# Index_Registers_-_1_1.net
KiCad netlist of a schematic drawn in EAGLE
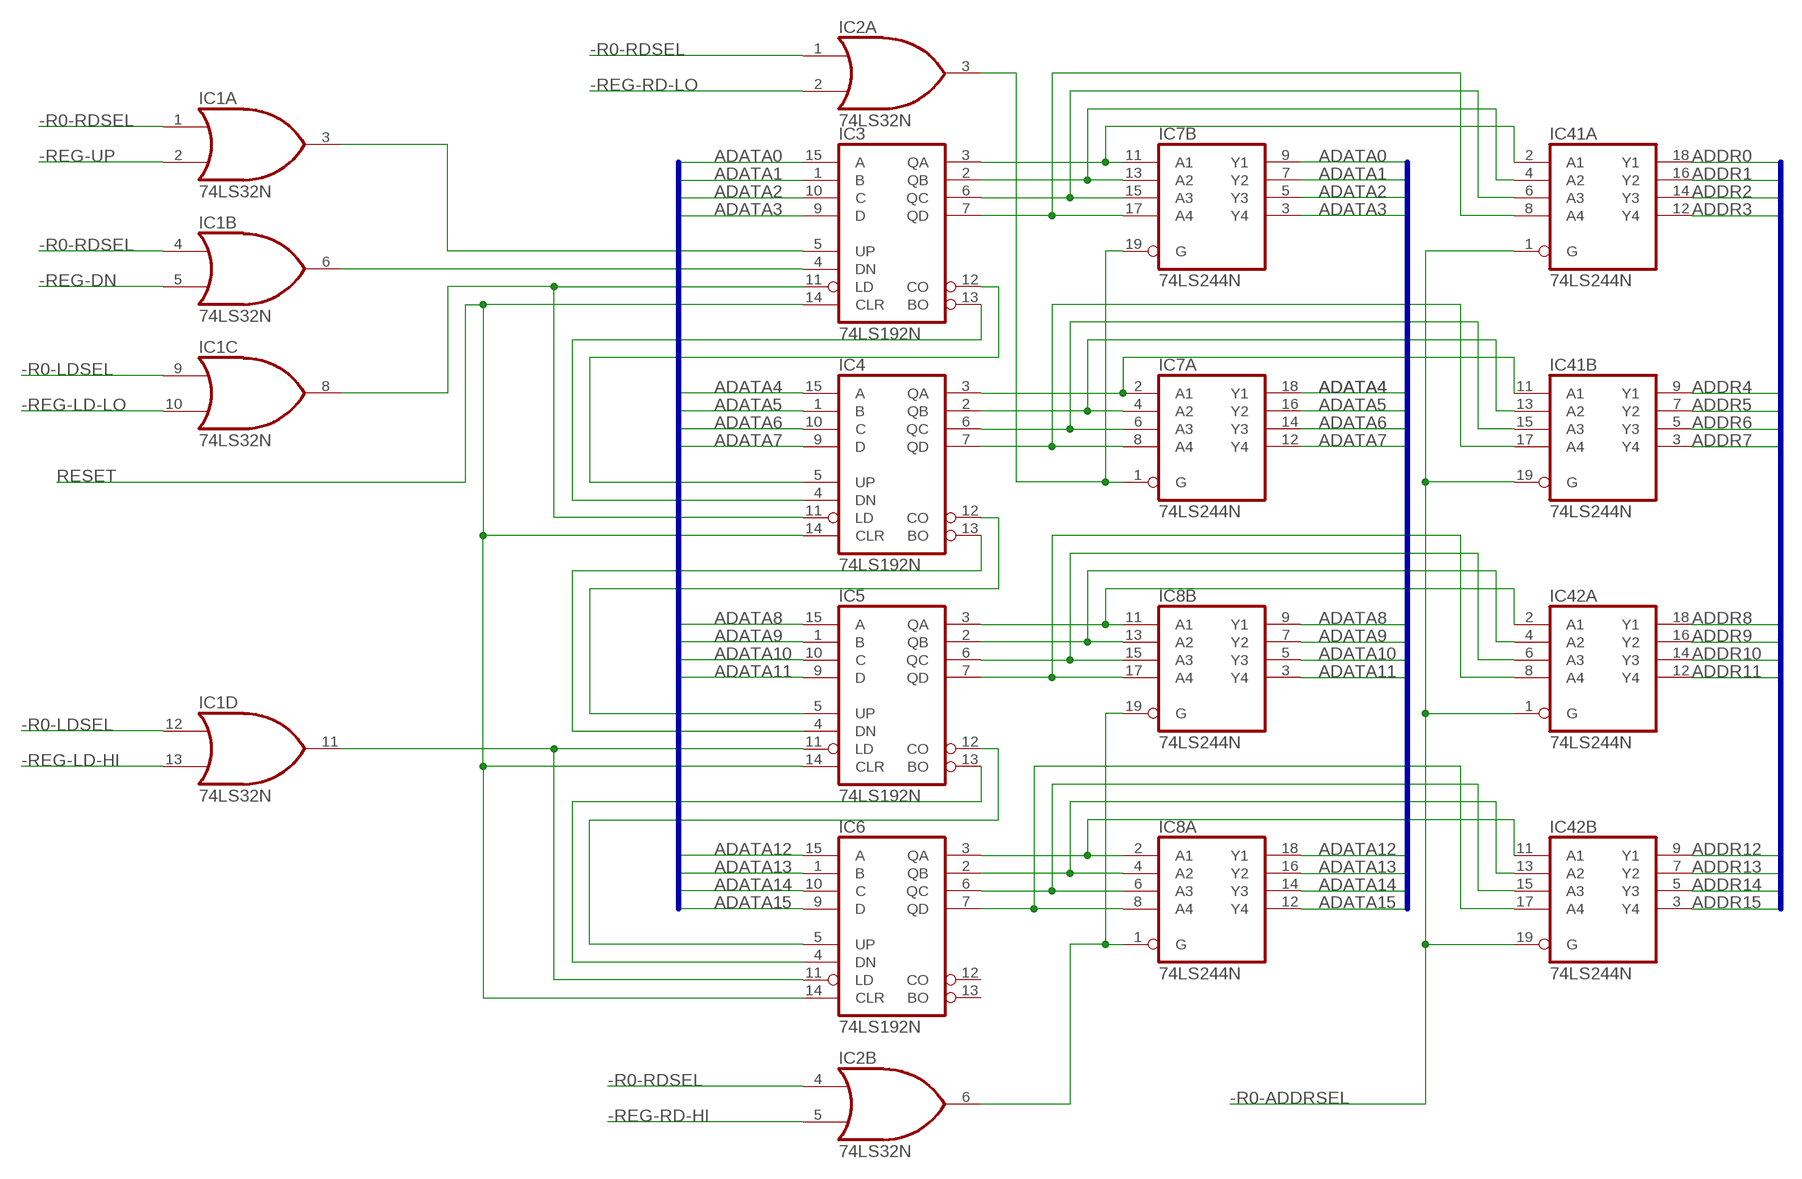
[diagram p0: schematic, sheet 1]
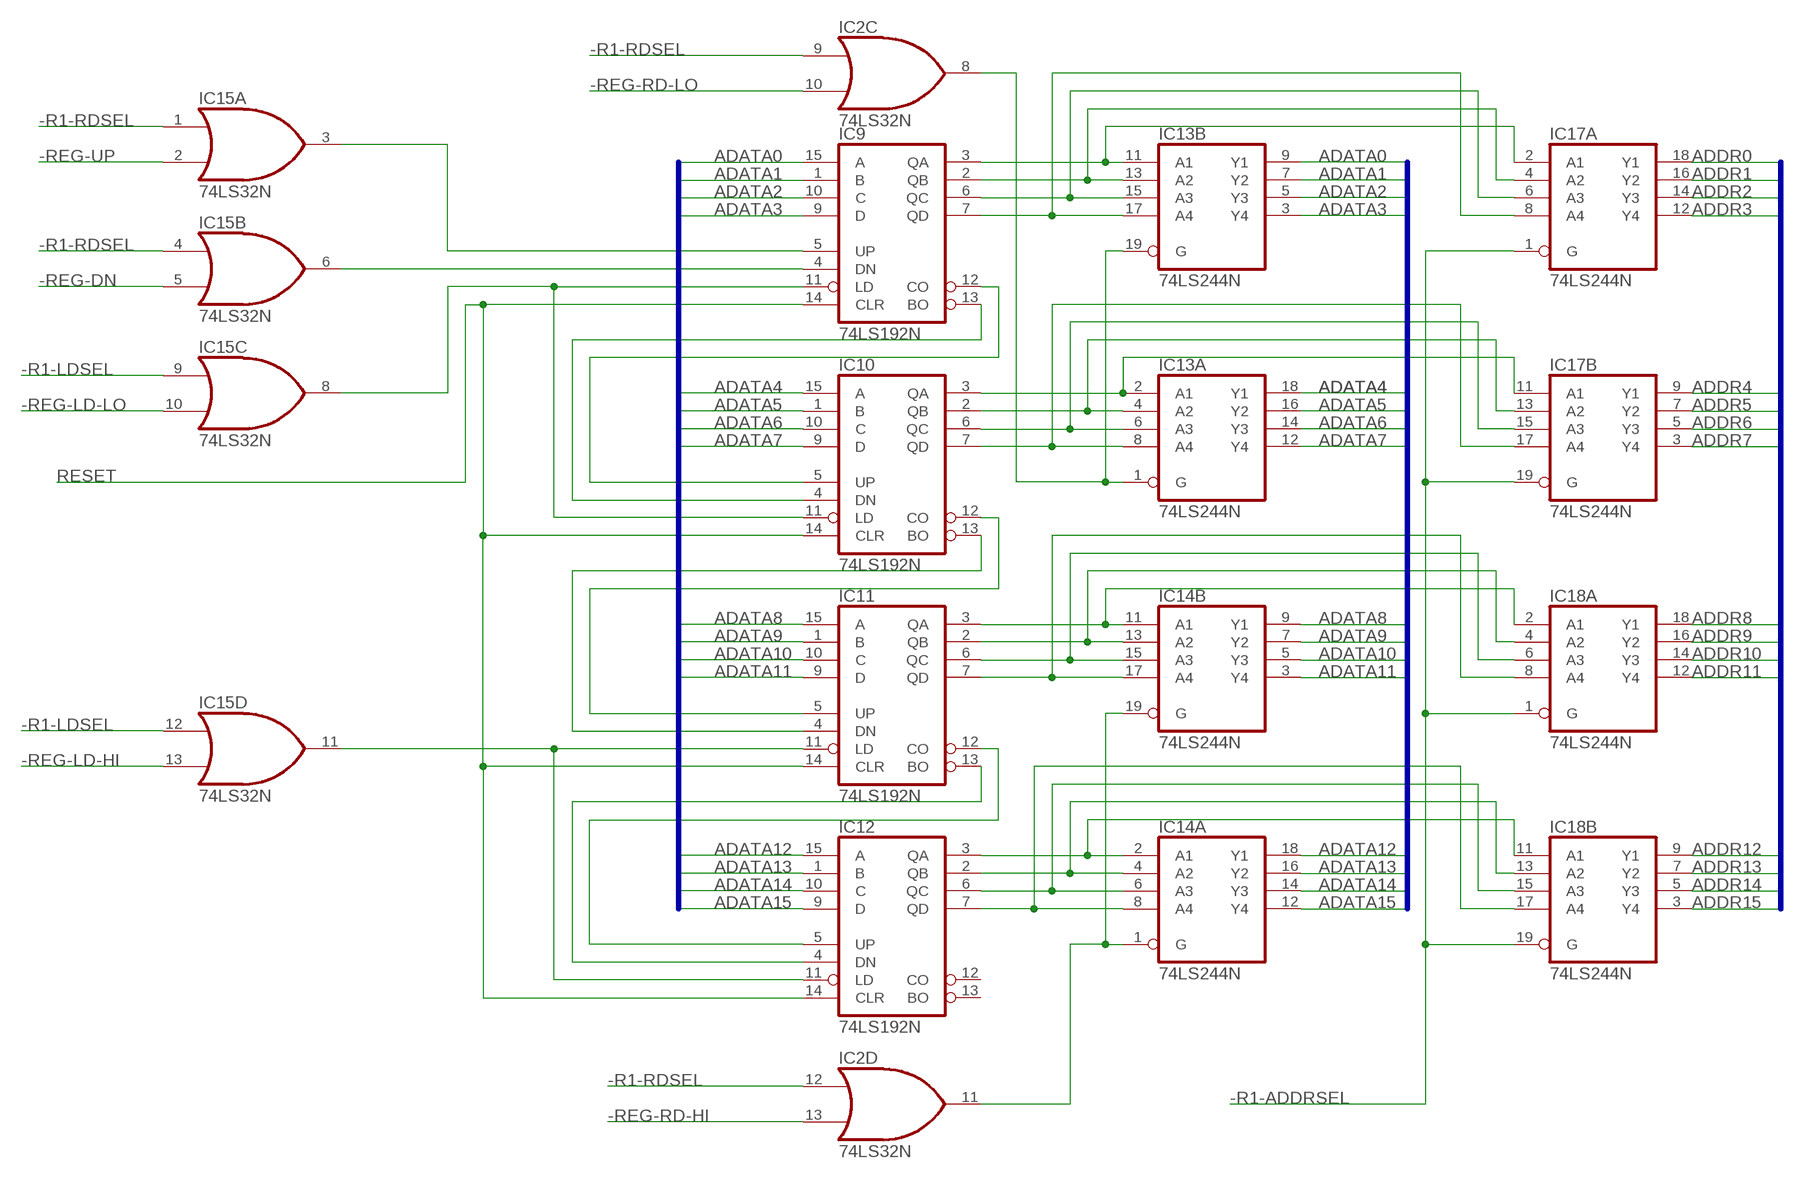
[diagram p1: schematic, sheet 2]
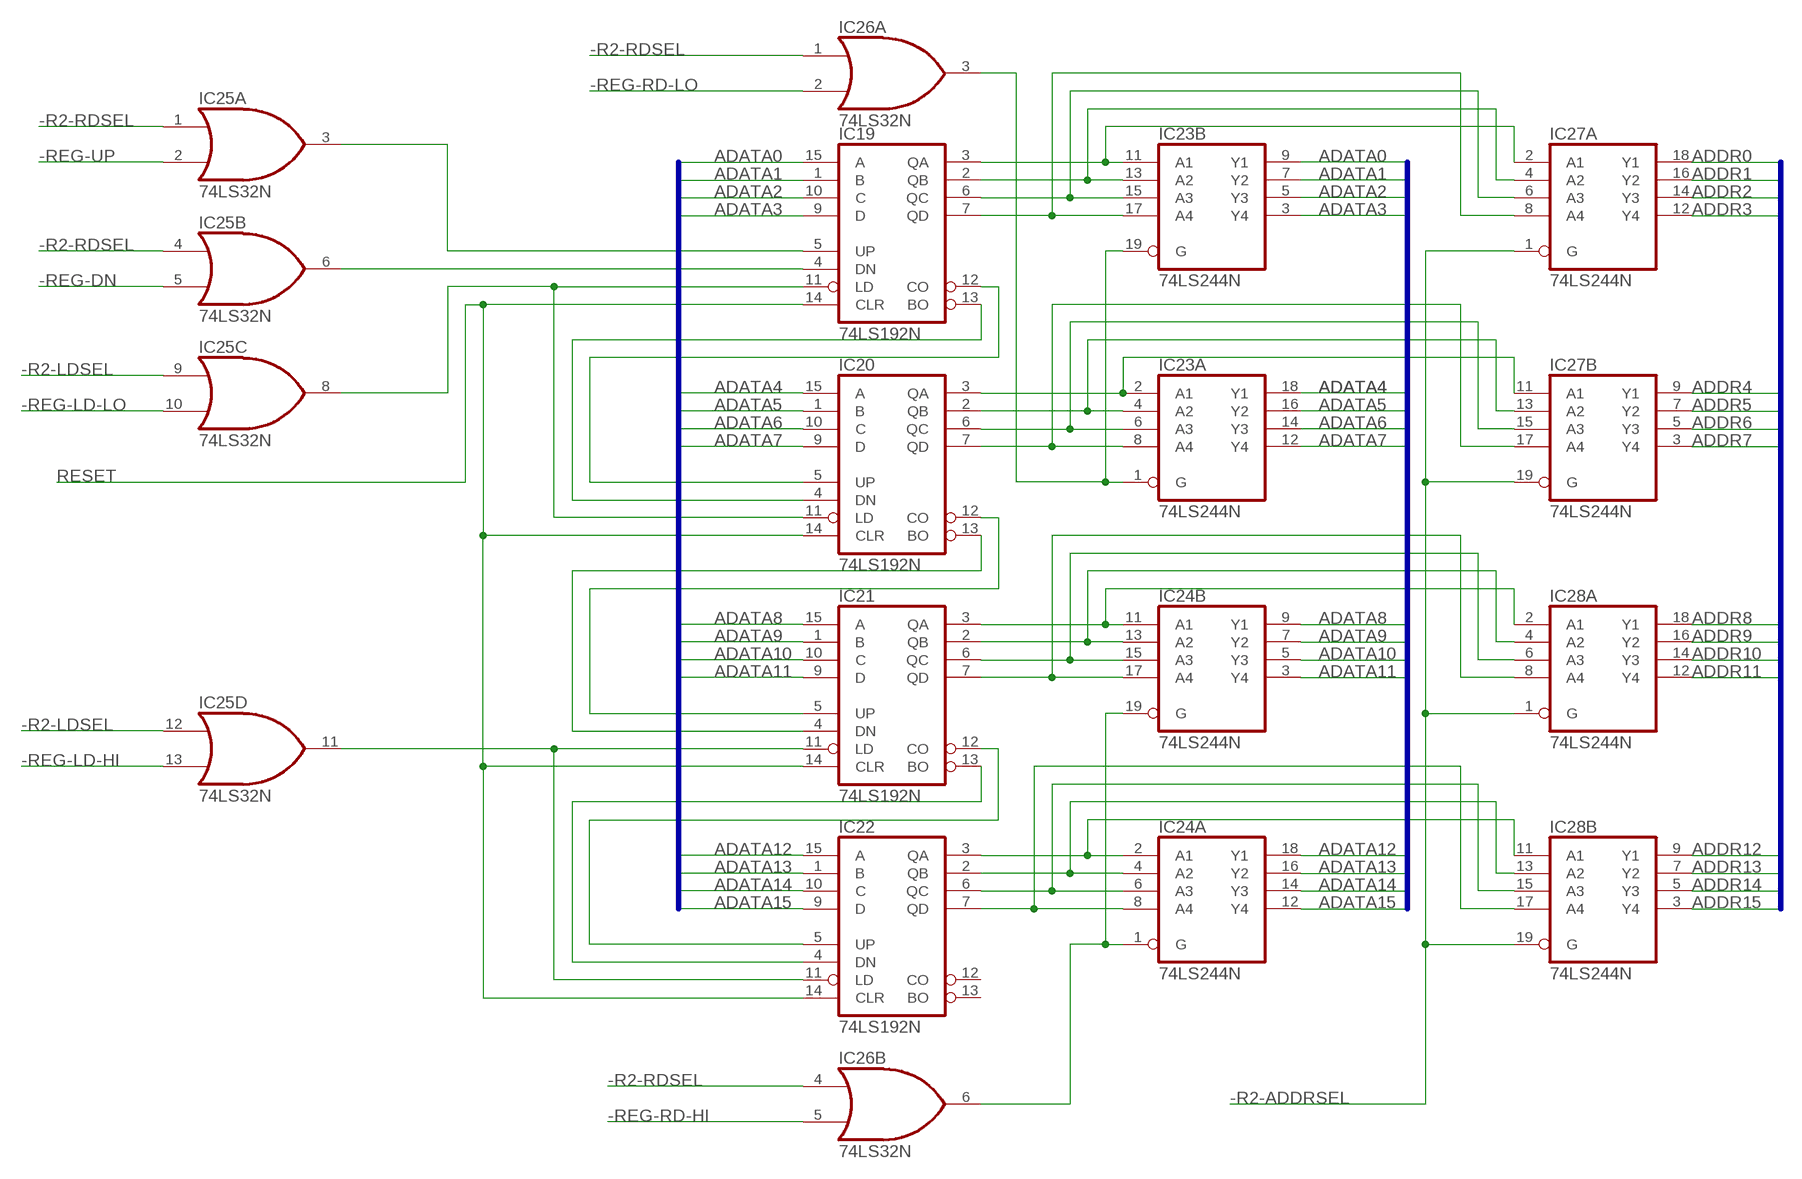
[diagram p2: schematic, sheet 3]
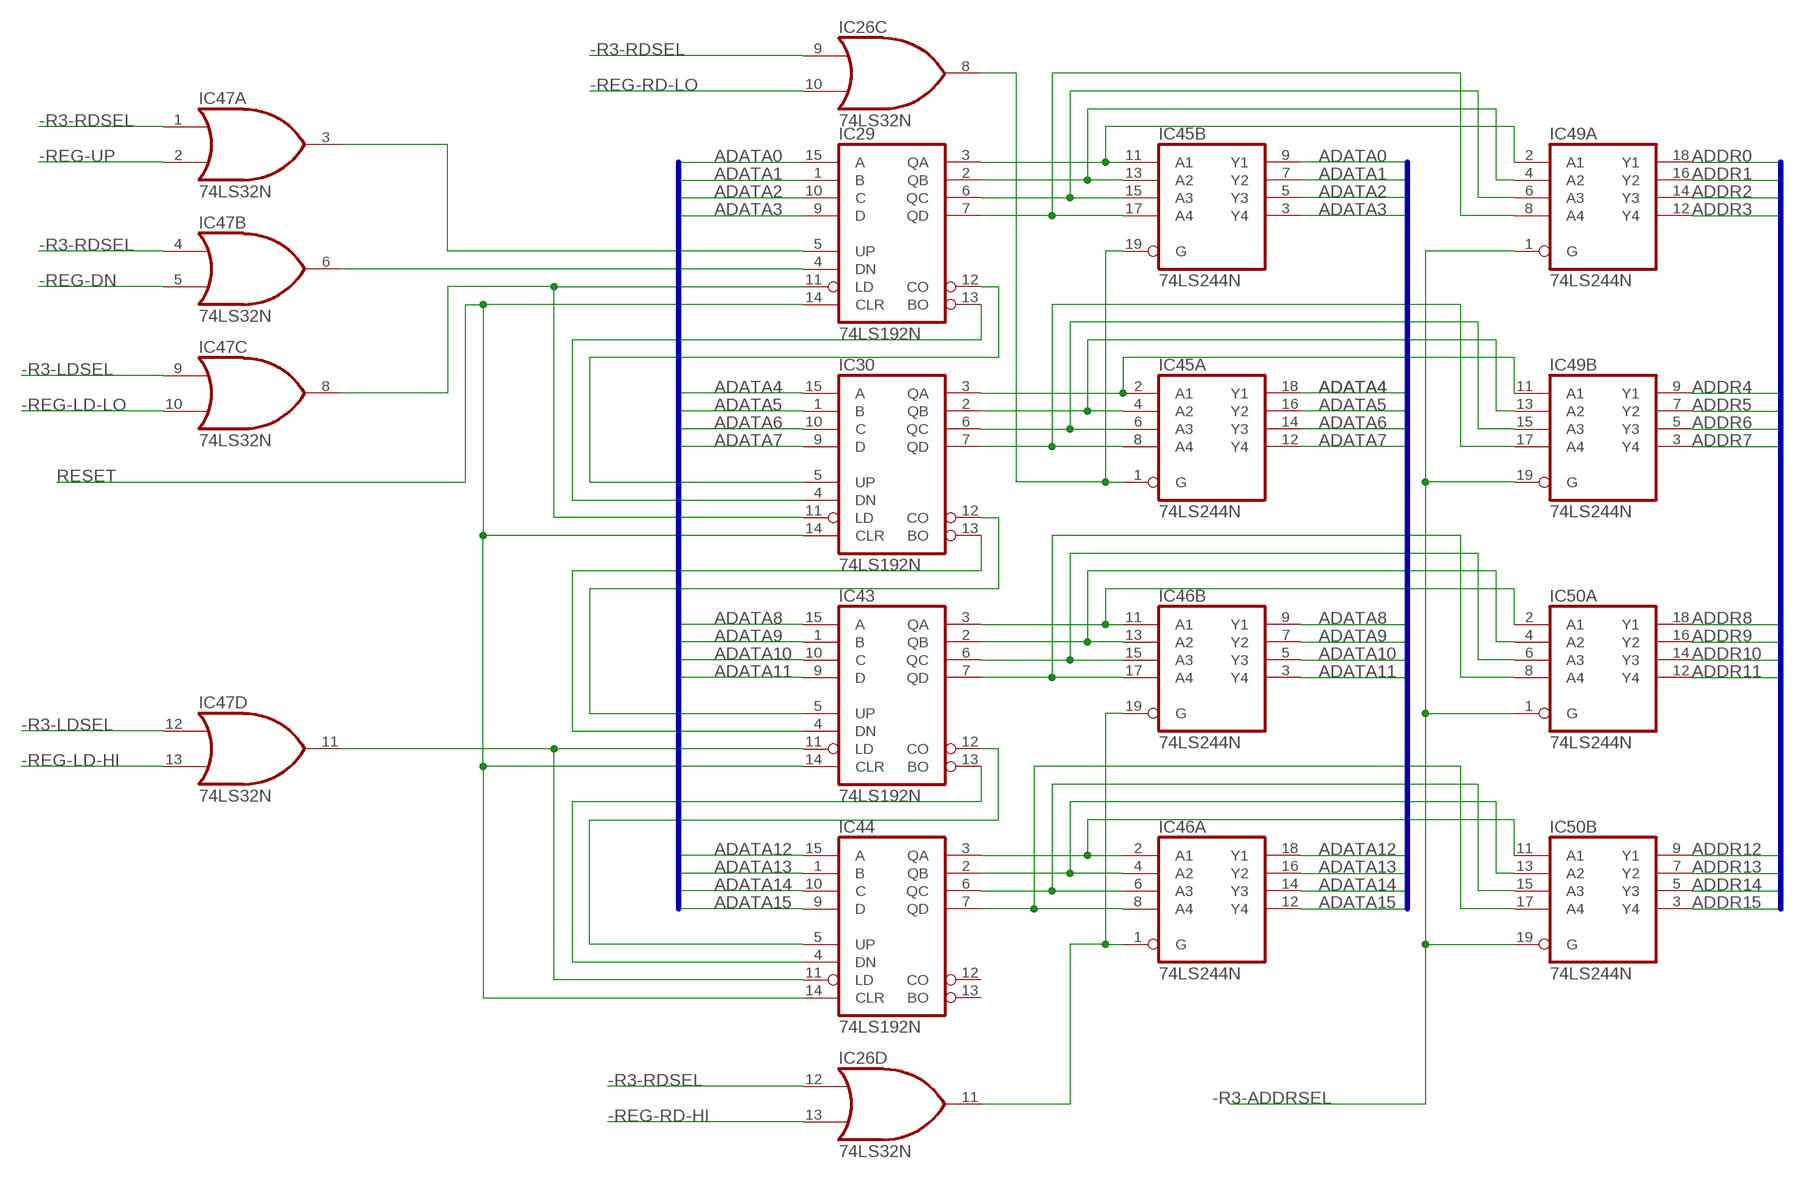
[diagram p3: schematic, sheet 4]
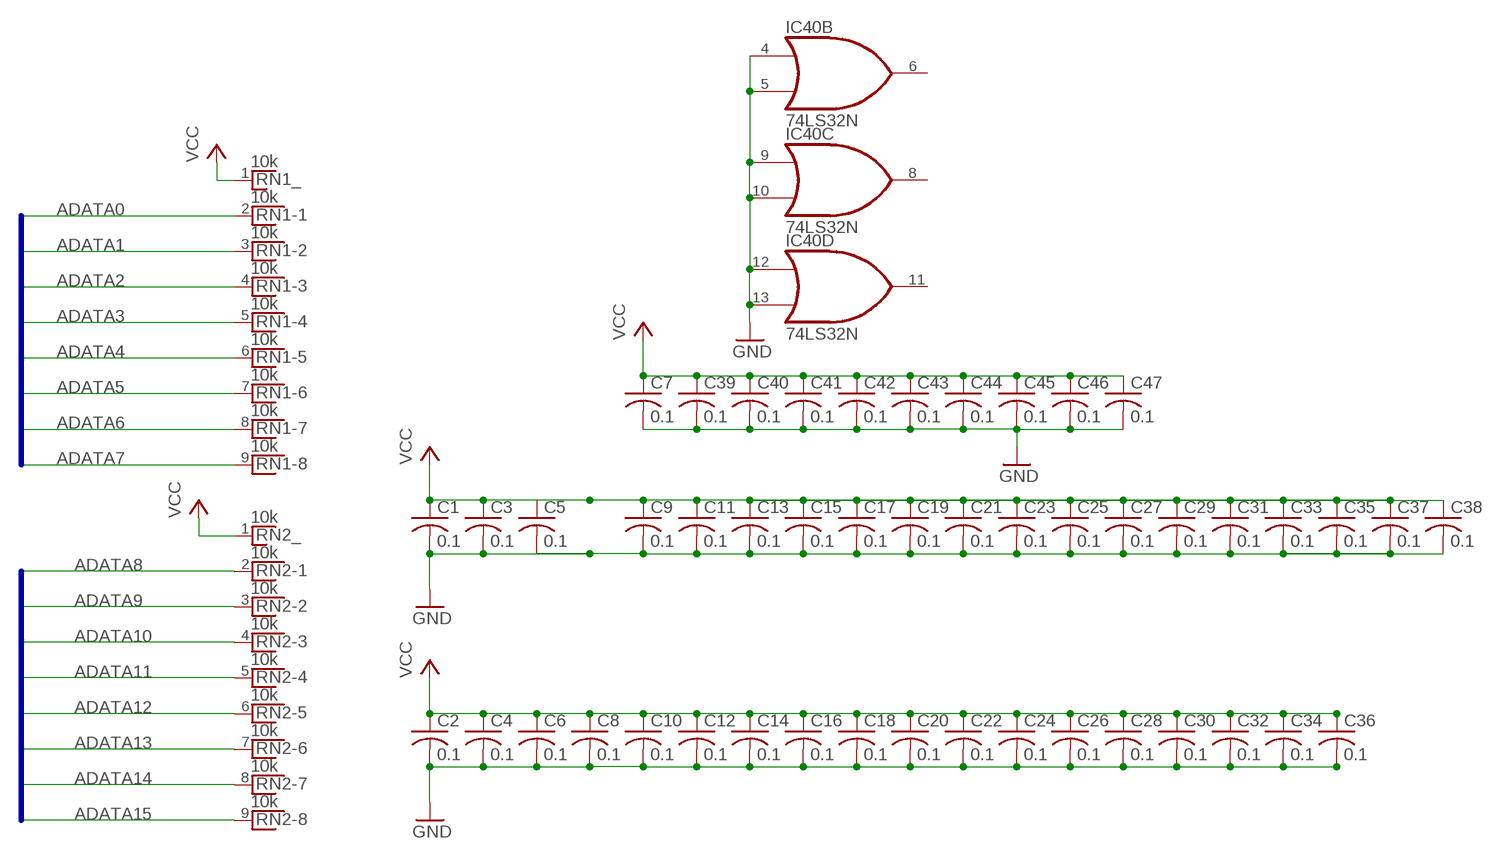
[diagram p4: schematic, sheet 5]
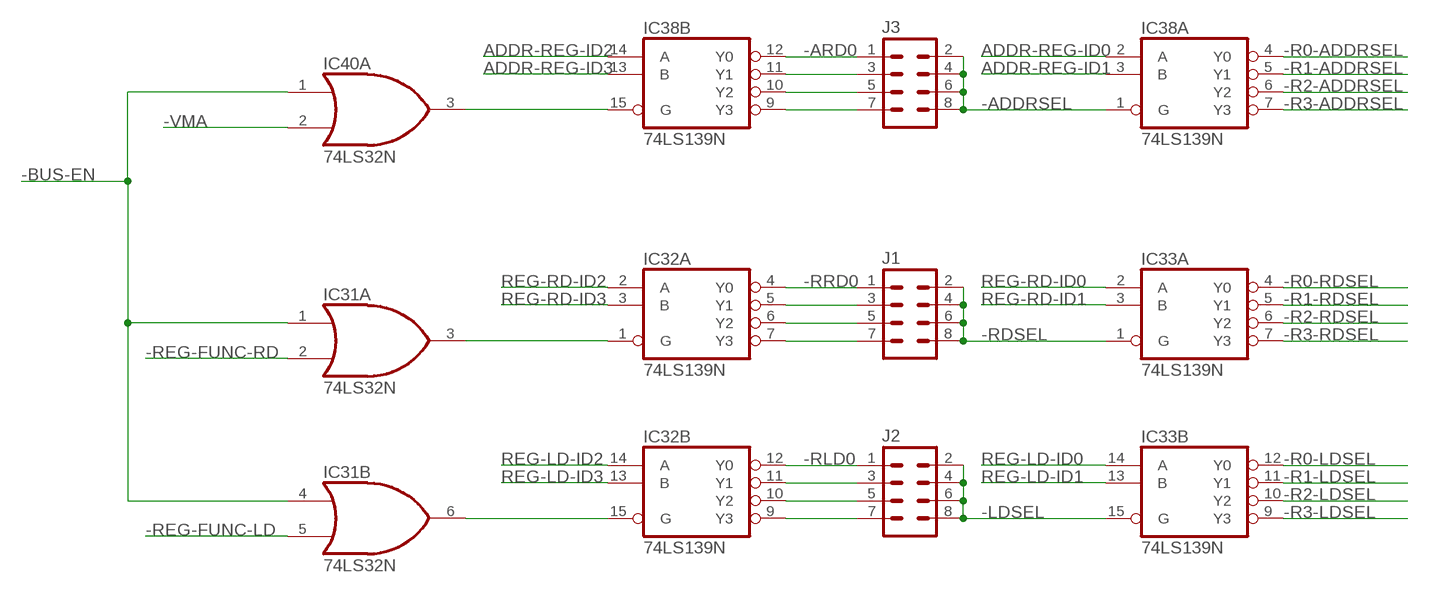
[diagram p5: schematic, sheet 6]
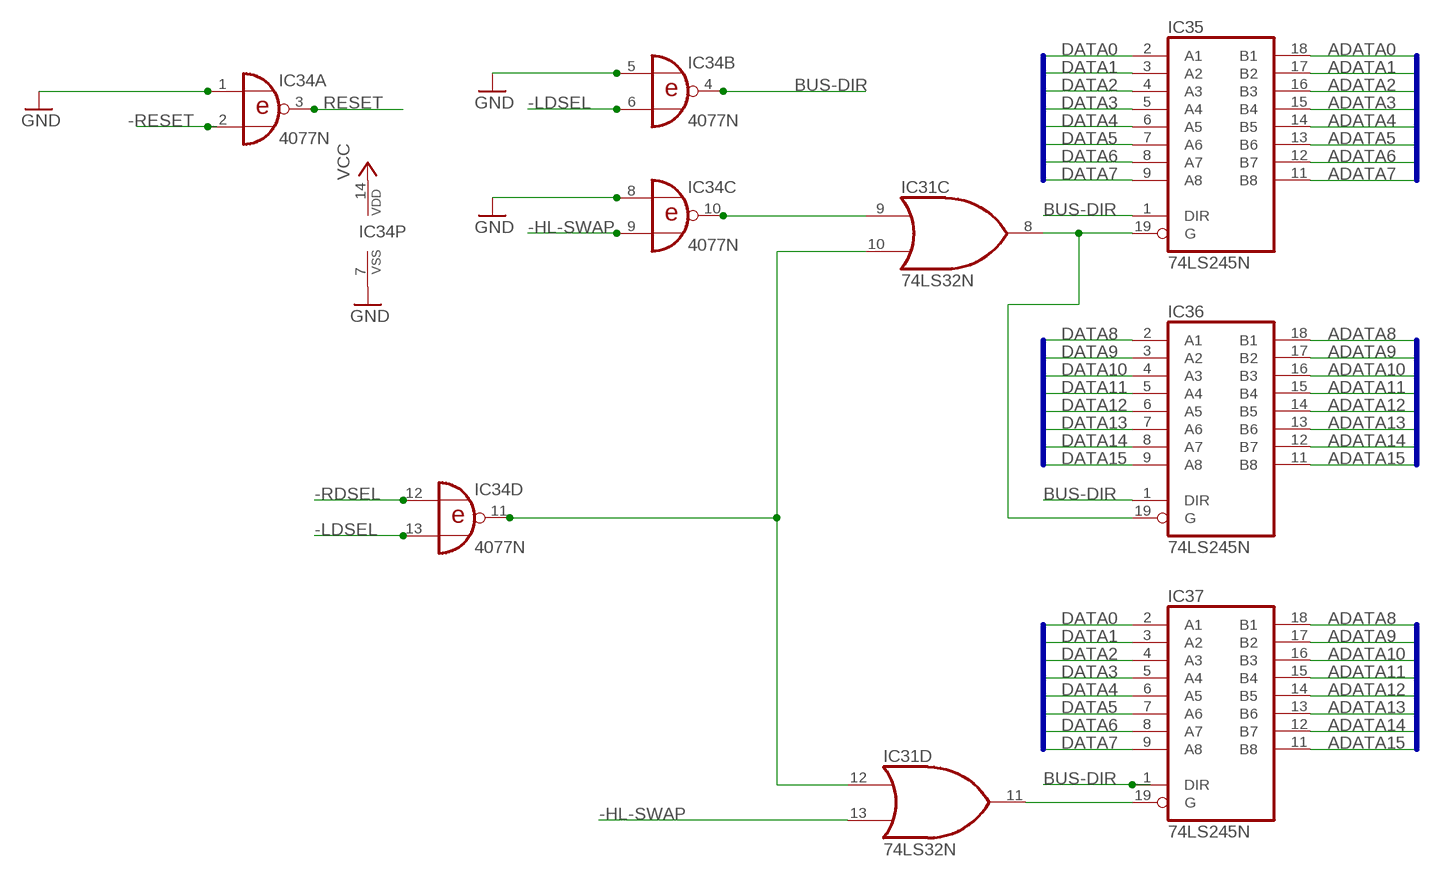
[diagram p6: schematic, sheet 7]
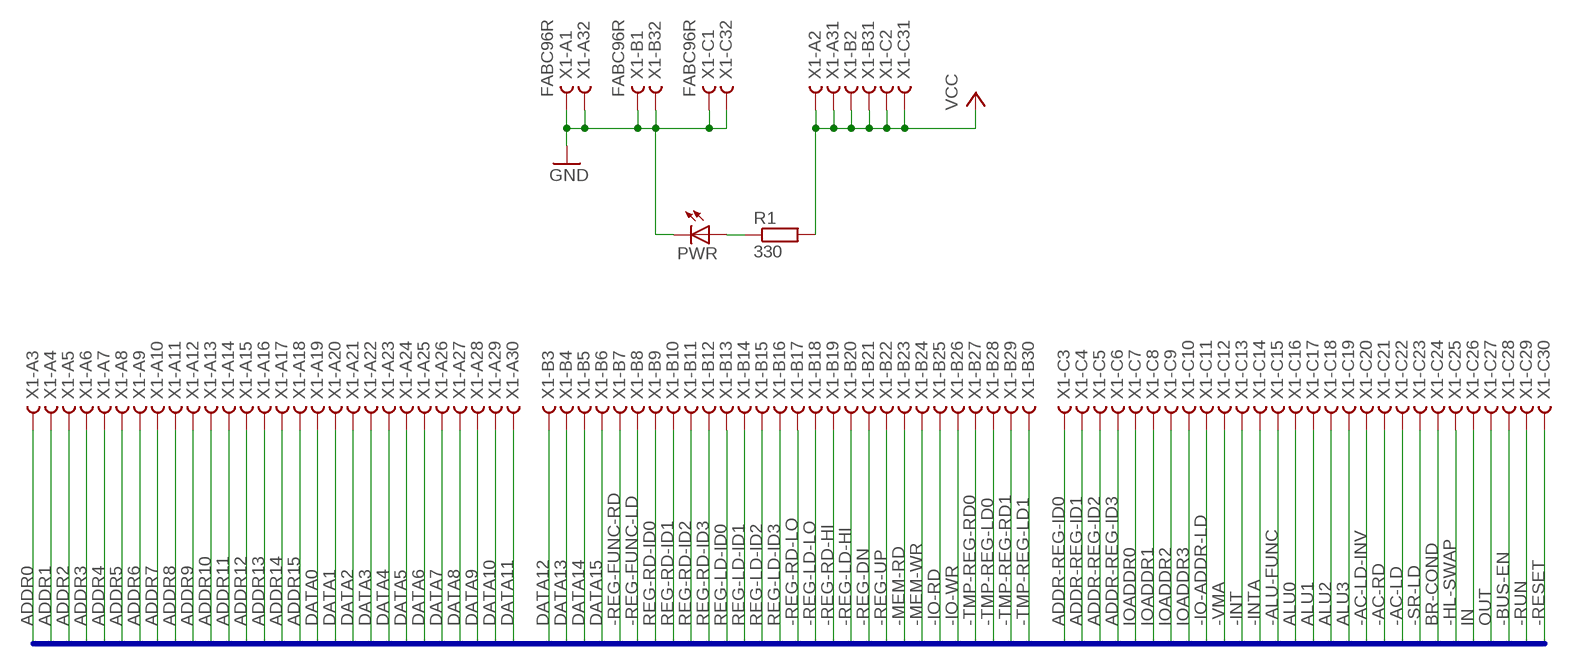
[diagram p7: schematic, sheet 8]

(export (version "E")
  (design (tool "Eeschema 10.0.6"))
  (components
    (comp (ref "PWR")
      (value "LED5MM")
      (footprint "eagle-import:LED5MM")
      (libsource (lib "eagle-import") (part "LED5MM"))
    )
    (comp (ref "R1")
      (value "330")
      (footprint "eagle-import:0207_10")
      (libsource (lib "eagle-import") (part "R0207/10"))
    )
    (comp (ref "X1")
      (value "FABC96R")
      (footprint "eagle-import:FABC96R")
      (libsource (lib "eagle-import") (part "FABC96R"))
    )
    (comp (ref "C1")
      (value "0.1")
      (footprint "eagle-import:C025-040X050")
      (libsource (lib "eagle-import") (part "C-US025-040X050"))
    )
    (comp (ref "C2")
      (value "0.1")
      (footprint "eagle-import:C025-040X050")
      (libsource (lib "eagle-import") (part "C-US025-040X050"))
    )
    (comp (ref "C3")
      (value "0.1")
      (footprint "eagle-import:C025-040X050")
      (libsource (lib "eagle-import") (part "C-US025-040X050"))
    )
    (comp (ref "C4")
      (value "0.1")
      (footprint "eagle-import:C025-040X050")
      (libsource (lib "eagle-import") (part "C-US025-040X050"))
    )
    (comp (ref "C5")
      (value "0.1")
      (footprint "eagle-import:C025-040X050")
      (libsource (lib "eagle-import") (part "C-US025-040X050"))
    )
    (comp (ref "C6")
      (value "0.1")
      (footprint "eagle-import:C025-040X050")
      (libsource (lib "eagle-import") (part "C-US025-040X050"))
    )
    (comp (ref "C7")
      (value "0.1")
      (footprint "eagle-import:C025-040X050")
      (libsource (lib "eagle-import") (part "C-US025-040X050"))
    )
    (comp (ref "C8")
      (value "0.1")
      (footprint "eagle-import:C025-040X050")
      (libsource (lib "eagle-import") (part "C-US025-040X050"))
    )
    (comp (ref "C9")
      (value "0.1")
      (footprint "eagle-import:C025-040X050")
      (libsource (lib "eagle-import") (part "C-US025-040X050"))
    )
    (comp (ref "C10")
      (value "0.1")
      (footprint "eagle-import:C025-040X050")
      (libsource (lib "eagle-import") (part "C-US025-040X050"))
    )
    (comp (ref "C11")
      (value "0.1")
      (footprint "eagle-import:C025-040X050")
      (libsource (lib "eagle-import") (part "C-US025-040X050"))
    )
    (comp (ref "C12")
      (value "0.1")
      (footprint "eagle-import:C025-040X050")
      (libsource (lib "eagle-import") (part "C-US025-040X050"))
    )
    (comp (ref "C13")
      (value "0.1")
      (footprint "eagle-import:C025-040X050")
      (libsource (lib "eagle-import") (part "C-US025-040X050"))
    )
    (comp (ref "C14")
      (value "0.1")
      (footprint "eagle-import:C025-040X050")
      (libsource (lib "eagle-import") (part "C-US025-040X050"))
    )
    (comp (ref "C15")
      (value "0.1")
      (footprint "eagle-import:C025-040X050")
      (libsource (lib "eagle-import") (part "C-US025-040X050"))
    )
    (comp (ref "C16")
      (value "0.1")
      (footprint "eagle-import:C025-040X050")
      (libsource (lib "eagle-import") (part "C-US025-040X050"))
    )
    (comp (ref "C17")
      (value "0.1")
      (footprint "eagle-import:C025-040X050")
      (libsource (lib "eagle-import") (part "C-US025-040X050"))
    )
    (comp (ref "C18")
      (value "0.1")
      (footprint "eagle-import:C025-040X050")
      (libsource (lib "eagle-import") (part "C-US025-040X050"))
    )
    (comp (ref "C19")
      (value "0.1")
      (footprint "eagle-import:C025-040X050")
      (libsource (lib "eagle-import") (part "C-US025-040X050"))
    )
    (comp (ref "C20")
      (value "0.1")
      (footprint "eagle-import:C025-040X050")
      (libsource (lib "eagle-import") (part "C-US025-040X050"))
    )
    (comp (ref "C21")
      (value "0.1")
      (footprint "eagle-import:C025-040X050")
      (libsource (lib "eagle-import") (part "C-US025-040X050"))
    )
    (comp (ref "C22")
      (value "0.1")
      (footprint "eagle-import:C025-040X050")
      (libsource (lib "eagle-import") (part "C-US025-040X050"))
    )
    (comp (ref "C23")
      (value "0.1")
      (footprint "eagle-import:C025-040X050")
      (libsource (lib "eagle-import") (part "C-US025-040X050"))
    )
    (comp (ref "C24")
      (value "0.1")
      (footprint "eagle-import:C025-040X050")
      (libsource (lib "eagle-import") (part "C-US025-040X050"))
    )
    (comp (ref "C25")
      (value "0.1")
      (footprint "eagle-import:C025-040X050")
      (libsource (lib "eagle-import") (part "C-US025-040X050"))
    )
    (comp (ref "C26")
      (value "0.1")
      (footprint "eagle-import:C025-040X050")
      (libsource (lib "eagle-import") (part "C-US025-040X050"))
    )
    (comp (ref "C27")
      (value "0.1")
      (footprint "eagle-import:C025-040X050")
      (libsource (lib "eagle-import") (part "C-US025-040X050"))
    )
    (comp (ref "C28")
      (value "0.1")
      (footprint "eagle-import:C025-040X050")
      (libsource (lib "eagle-import") (part "C-US025-040X050"))
    )
    (comp (ref "C29")
      (value "0.1")
      (footprint "eagle-import:C025-040X050")
      (libsource (lib "eagle-import") (part "C-US025-040X050"))
    )
    (comp (ref "C30")
      (value "0.1")
      (footprint "eagle-import:C025-040X050")
      (libsource (lib "eagle-import") (part "C-US025-040X050"))
    )
    (comp (ref "C31")
      (value "0.1")
      (footprint "eagle-import:C025-040X050")
      (libsource (lib "eagle-import") (part "C-US025-040X050"))
    )
    (comp (ref "C32")
      (value "0.1")
      (footprint "eagle-import:C025-040X050")
      (libsource (lib "eagle-import") (part "C-US025-040X050"))
    )
    (comp (ref "C33")
      (value "0.1")
      (footprint "eagle-import:C025-040X050")
      (libsource (lib "eagle-import") (part "C-US025-040X050"))
    )
    (comp (ref "C34")
      (value "0.1")
      (footprint "eagle-import:C025-040X050")
      (libsource (lib "eagle-import") (part "C-US025-040X050"))
    )
    (comp (ref "C35")
      (value "0.1")
      (footprint "eagle-import:C025-040X050")
      (libsource (lib "eagle-import") (part "C-US025-040X050"))
    )
    (comp (ref "C36")
      (value "0.1")
      (footprint "eagle-import:C025-040X050")
      (libsource (lib "eagle-import") (part "C-US025-040X050"))
    )
    (comp (ref "C37")
      (value "0.1")
      (footprint "eagle-import:C025-040X050")
      (libsource (lib "eagle-import") (part "C-US025-040X050"))
    )
    (comp (ref "C38")
      (value "0.1")
      (footprint "eagle-import:C025-040X050")
      (libsource (lib "eagle-import") (part "C-US025-040X050"))
    )
    (comp (ref "C39")
      (value "0.1")
      (footprint "eagle-import:C025-040X050")
      (libsource (lib "eagle-import") (part "C-US025-040X050"))
    )
    (comp (ref "C40")
      (value "0.1")
      (footprint "eagle-import:C025-040X050")
      (libsource (lib "eagle-import") (part "C-US025-040X050"))
    )
    (comp (ref "C41")
      (value "0.1")
      (footprint "eagle-import:C025-040X050")
      (libsource (lib "eagle-import") (part "C-US025-040X050"))
    )
    (comp (ref "C42")
      (value "0.1")
      (footprint "eagle-import:C025-040X050")
      (libsource (lib "eagle-import") (part "C-US025-040X050"))
    )
    (comp (ref "C43")
      (value "0.1")
      (footprint "eagle-import:C025-040X050")
      (libsource (lib "eagle-import") (part "C-US025-040X050"))
    )
    (comp (ref "C44")
      (value "0.1")
      (footprint "eagle-import:C025-040X050")
      (libsource (lib "eagle-import") (part "C-US025-040X050"))
    )
    (comp (ref "C45")
      (value "0.1")
      (footprint "eagle-import:C025-040X050")
      (libsource (lib "eagle-import") (part "C-US025-040X050"))
    )
    (comp (ref "C46")
      (value "0.1")
      (footprint "eagle-import:C025-040X050")
      (libsource (lib "eagle-import") (part "C-US025-040X050"))
    )
    (comp (ref "C47")
      (value "0.1")
      (footprint "eagle-import:C025-040X050")
      (libsource (lib "eagle-import") (part "C-US025-040X050"))
    )
    (comp (ref "IC40")
      (value "74LS32N")
      (footprint "eagle-import:DIL14")
      (libsource (lib "eagle-import") (part "7432NLS"))
    )
    (comp (ref "RN1")
      (value "10k")
      (footprint "eagle-import:RN-9")
      (libsource (lib "eagle-import") (part "RNX8"))
    )
    (comp (ref "RN2")
      (value "10k")
      (footprint "eagle-import:RN-9")
      (libsource (lib "eagle-import") (part "RNX8"))
    )
    (comp (ref "IC31")
      (value "74LS32N")
      (footprint "eagle-import:DIL14")
      (libsource (lib "eagle-import") (part "7432NLS"))
    )
    (comp (ref "IC34")
      (value "4077N")
      (footprint "eagle-import:DIL14")
      (libsource (lib "eagle-import") (part "4077N"))
    )
    (comp (ref "IC35")
      (value "74LS245N")
      (footprint "eagle-import:DIL20")
      (libsource (lib "eagle-import") (part "74245NLS"))
    )
    (comp (ref "IC36")
      (value "74LS245N")
      (footprint "eagle-import:DIL20")
      (libsource (lib "eagle-import") (part "74245NLS"))
    )
    (comp (ref "IC37")
      (value "74LS245N")
      (footprint "eagle-import:DIL20")
      (libsource (lib "eagle-import") (part "74245NLS"))
    )
    (comp (ref "IC19")
      (value "74LS192N")
      (footprint "eagle-import:DIL16")
      (libsource (lib "eagle-import") (part "74192NLS"))
    )
    (comp (ref "IC20")
      (value "74LS192N")
      (footprint "eagle-import:DIL16")
      (libsource (lib "eagle-import") (part "74192NLS"))
    )
    (comp (ref "IC21")
      (value "74LS192N")
      (footprint "eagle-import:DIL16")
      (libsource (lib "eagle-import") (part "74192NLS"))
    )
    (comp (ref "IC22")
      (value "74LS192N")
      (footprint "eagle-import:DIL16")
      (libsource (lib "eagle-import") (part "74192NLS"))
    )
    (comp (ref "IC23")
      (value "74LS244N")
      (footprint "eagle-import:DIL20")
      (libsource (lib "eagle-import") (part "74xx-us_74244NLS"))
    )
    (comp (ref "IC24")
      (value "74LS244N")
      (footprint "eagle-import:DIL20")
      (libsource (lib "eagle-import") (part "74xx-us_74244NLS"))
    )
    (comp (ref "IC25")
      (value "74LS32N")
      (footprint "eagle-import:DIL14")
      (libsource (lib "eagle-import") (part "7432NLS"))
    )
    (comp (ref "IC26")
      (value "74LS32N")
      (footprint "eagle-import:DIL14")
      (libsource (lib "eagle-import") (part "7432NLS"))
    )
    (comp (ref "IC27")
      (value "74LS244N")
      (footprint "eagle-import:DIL20")
      (libsource (lib "eagle-import") (part "74xx-us_88_74244NLS"))
    )
    (comp (ref "IC28")
      (value "74LS244N")
      (footprint "eagle-import:DIL20")
      (libsource (lib "eagle-import") (part "74xx-us_88_74244NLS"))
    )
    (comp (ref "IC1")
      (value "74LS32N")
      (footprint "eagle-import:DIL14")
      (libsource (lib "eagle-import") (part "7432NLS"))
    )
    (comp (ref "IC2")
      (value "74LS32N")
      (footprint "eagle-import:DIL14")
      (libsource (lib "eagle-import") (part "7432NLS"))
    )
    (comp (ref "IC3")
      (value "74LS192N")
      (footprint "eagle-import:DIL16")
      (libsource (lib "eagle-import") (part "74192NLS"))
    )
    (comp (ref "IC4")
      (value "74LS192N")
      (footprint "eagle-import:DIL16")
      (libsource (lib "eagle-import") (part "74192NLS"))
    )
    (comp (ref "IC5")
      (value "74LS192N")
      (footprint "eagle-import:DIL16")
      (libsource (lib "eagle-import") (part "74192NLS"))
    )
    (comp (ref "IC6")
      (value "74LS192N")
      (footprint "eagle-import:DIL16")
      (libsource (lib "eagle-import") (part "74192NLS"))
    )
    (comp (ref "IC7")
      (value "74LS244N")
      (footprint "eagle-import:DIL20")
      (libsource (lib "eagle-import") (part "74xx-us_74244NLS"))
    )
    (comp (ref "IC8")
      (value "74LS244N")
      (footprint "eagle-import:DIL20")
      (libsource (lib "eagle-import") (part "74xx-us_74244NLS"))
    )
    (comp (ref "IC41")
      (value "74LS244N")
      (footprint "eagle-import:DIL20")
      (libsource (lib "eagle-import") (part "74xx-us_88_74244NLS"))
    )
    (comp (ref "IC42")
      (value "74LS244N")
      (footprint "eagle-import:DIL20")
      (libsource (lib "eagle-import") (part "74xx-us_88_74244NLS"))
    )
    (comp (ref "IC32")
      (value "74LS139N")
      (footprint "eagle-import:DIL16")
      (libsource (lib "eagle-import") (part "74139NLS"))
    )
    (comp (ref "IC33")
      (value "74LS139N")
      (footprint "eagle-import:DIL16")
      (libsource (lib "eagle-import") (part "74139NLS"))
    )
    (comp (ref "IC38")
      (value "74LS139N")
      (footprint "eagle-import:DIL16")
      (libsource (lib "eagle-import") (part "74139NLS"))
    )
    (comp (ref "J1")
      (value "M04X2")
      (footprint "eagle-import:2X4")
      (libsource (lib "eagle-import") (part "M04X2"))
    )
    (comp (ref "J2")
      (value "M04X2")
      (footprint "eagle-import:2X4")
      (libsource (lib "eagle-import") (part "M04X2"))
    )
    (comp (ref "J3")
      (value "M04X2")
      (footprint "eagle-import:2X4")
      (libsource (lib "eagle-import") (part "M04X2"))
    )
    (comp (ref "IC29")
      (value "74LS192N")
      (footprint "eagle-import:DIL16")
      (libsource (lib "eagle-import") (part "74192NLS"))
    )
    (comp (ref "IC30")
      (value "74LS192N")
      (footprint "eagle-import:DIL16")
      (libsource (lib "eagle-import") (part "74192NLS"))
    )
    (comp (ref "IC43")
      (value "74LS192N")
      (footprint "eagle-import:DIL16")
      (libsource (lib "eagle-import") (part "74192NLS"))
    )
    (comp (ref "IC44")
      (value "74LS192N")
      (footprint "eagle-import:DIL16")
      (libsource (lib "eagle-import") (part "74192NLS"))
    )
    (comp (ref "IC45")
      (value "74LS244N")
      (footprint "eagle-import:DIL20")
      (libsource (lib "eagle-import") (part "74xx-us_74244NLS"))
    )
    (comp (ref "IC46")
      (value "74LS244N")
      (footprint "eagle-import:DIL20")
      (libsource (lib "eagle-import") (part "74xx-us_74244NLS"))
    )
    (comp (ref "IC47")
      (value "74LS32N")
      (footprint "eagle-import:DIL14")
      (libsource (lib "eagle-import") (part "7432NLS"))
    )
    (comp (ref "IC49")
      (value "74LS244N")
      (footprint "eagle-import:DIL20")
      (libsource (lib "eagle-import") (part "74xx-us_88_74244NLS"))
    )
    (comp (ref "IC50")
      (value "74LS244N")
      (footprint "eagle-import:DIL20")
      (libsource (lib "eagle-import") (part "74xx-us_88_74244NLS"))
    )
    (comp (ref "IC9")
      (value "74LS192N")
      (footprint "eagle-import:DIL16")
      (libsource (lib "eagle-import") (part "74192NLS"))
    )
    (comp (ref "IC10")
      (value "74LS192N")
      (footprint "eagle-import:DIL16")
      (libsource (lib "eagle-import") (part "74192NLS"))
    )
    (comp (ref "IC11")
      (value "74LS192N")
      (footprint "eagle-import:DIL16")
      (libsource (lib "eagle-import") (part "74192NLS"))
    )
    (comp (ref "IC12")
      (value "74LS192N")
      (footprint "eagle-import:DIL16")
      (libsource (lib "eagle-import") (part "74192NLS"))
    )
    (comp (ref "IC13")
      (value "74LS244N")
      (footprint "eagle-import:DIL20")
      (libsource (lib "eagle-import") (part "74xx-us_74244NLS"))
    )
    (comp (ref "IC14")
      (value "74LS244N")
      (footprint "eagle-import:DIL20")
      (libsource (lib "eagle-import") (part "74xx-us_74244NLS"))
    )
    (comp (ref "IC15")
      (value "74LS32N")
      (footprint "eagle-import:DIL14")
      (libsource (lib "eagle-import") (part "7432NLS"))
    )
    (comp (ref "IC17")
      (value "74LS244N")
      (footprint "eagle-import:DIL20")
      (libsource (lib "eagle-import") (part "74xx-us_88_74244NLS"))
    )
    (comp (ref "IC18")
      (value "74LS244N")
      (footprint "eagle-import:DIL20")
      (libsource (lib "eagle-import") (part "74xx-us_88_74244NLS"))
    )
  )
  (nets
    (net (code "1") (name "-AC-LD") (class "Default")
      (node (ref "X1") (pin "C22") (pinfunction "B_C22") (pintype "passive"))
    )
    (net (code "2") (name "-AC-LD-INV") (class "Default")
      (node (ref "X1") (pin "C20") (pinfunction "B_C20") (pintype "passive"))
    )
    (net (code "3") (name "-AC-RD") (class "Default")
      (node (ref "X1") (pin "C21") (pinfunction "B_C21") (pintype "passive"))
    )
    (net (code "4") (name "-ADDRSEL") (class "Default")
      (node (ref "IC38") (pin "1") (pinfunction "G_1") (pintype "input"))
      (node (ref "J3") (pin "2") (pinfunction "2_2") (pintype "passive"))
      (node (ref "J3") (pin "4") (pinfunction "4_4") (pintype "passive"))
      (node (ref "J3") (pin "6") (pinfunction "6_6") (pintype "passive"))
      (node (ref "J3") (pin "8") (pinfunction "8_8") (pintype "passive"))
    )
    (net (code "5") (name "-ALU-FUNC") (class "Default")
      (node (ref "X1") (pin "C15") (pinfunction "B_C15") (pintype "passive"))
    )
    (net (code "6") (name "-ARD0") (class "Default")
      (node (ref "IC38") (pin "12") (pinfunction "Y0_12") (pintype "output"))
      (node (ref "J3") (pin "1") (pinfunction "1_1") (pintype "passive"))
    )
    (net (code "7") (name "-BUS-EN") (class "Default")
      (node (ref "IC31") (pin "1") (pinfunction "I0_1") (pintype "input"))
      (node (ref "IC31") (pin "4") (pinfunction "I0_4") (pintype "input"))
      (node (ref "IC40") (pin "1") (pinfunction "I0_1") (pintype "input"))
      (node (ref "X1") (pin "C28") (pinfunction "B_C28") (pintype "passive"))
    )
    (net (code "8") (name "-HL-SWAP") (class "Default")
      (node (ref "IC31") (pin "13") (pinfunction "I1_13") (pintype "input"))
      (node (ref "IC34") (pin "9") (pinfunction "I1_9") (pintype "input"))
      (node (ref "X1") (pin "C25") (pinfunction "B_C25") (pintype "passive"))
    )
    (net (code "9") (name "-INT") (class "Default")
      (node (ref "X1") (pin "C13") (pinfunction "B_C13") (pintype "passive"))
    )
    (net (code "10") (name "-INTA") (class "Default")
      (node (ref "X1") (pin "C14") (pinfunction "B_C14") (pintype "passive"))
    )
    (net (code "11") (name "-IO-ADDR-LD") (class "Default")
      (node (ref "X1") (pin "C11") (pinfunction "B_C11") (pintype "passive"))
    )
    (net (code "12") (name "-IO-RD") (class "Default")
      (node (ref "X1") (pin "B25") (pinfunction "B_B25") (pintype "passive"))
    )
    (net (code "13") (name "-IO-WR") (class "Default")
      (node (ref "X1") (pin "B26") (pinfunction "B_B26") (pintype "passive"))
    )
    (net (code "14") (name "-LDSEL") (class "Default")
      (node (ref "IC33") (pin "15") (pinfunction "G_15") (pintype "input"))
      (node (ref "IC34") (pin "13") (pinfunction "I1_13") (pintype "input"))
      (node (ref "IC34") (pin "6") (pinfunction "I1_6") (pintype "input"))
      (node (ref "J2") (pin "2") (pinfunction "2_2") (pintype "passive"))
      (node (ref "J2") (pin "4") (pinfunction "4_4") (pintype "passive"))
      (node (ref "J2") (pin "6") (pinfunction "6_6") (pintype "passive"))
      (node (ref "J2") (pin "8") (pinfunction "8_8") (pintype "passive"))
    )
    (net (code "15") (name "-MEM-RD") (class "Default")
      (node (ref "X1") (pin "B23") (pinfunction "B_B23") (pintype "passive"))
    )
    (net (code "16") (name "-MEM-WR") (class "Default")
      (node (ref "X1") (pin "B24") (pinfunction "B_B24") (pintype "passive"))
    )
    (net (code "17") (name "-R0-ADDRSEL") (class "Default")
      (node (ref "IC38") (pin "4") (pinfunction "Y0_4") (pintype "output"))
      (node (ref "IC41") (pin "1") (pinfunction "G_1") (pintype "input"))
      (node (ref "IC41") (pin "19") (pinfunction "G_19") (pintype "input"))
      (node (ref "IC42") (pin "1") (pinfunction "G_1") (pintype "input"))
      (node (ref "IC42") (pin "19") (pinfunction "G_19") (pintype "input"))
    )
    (net (code "18") (name "-R0-LDSEL") (class "Default")
      (node (ref "IC1") (pin "12") (pinfunction "I0_12") (pintype "input"))
      (node (ref "IC1") (pin "9") (pinfunction "I0_9") (pintype "input"))
      (node (ref "IC33") (pin "12") (pinfunction "Y0_12") (pintype "output"))
    )
    (net (code "19") (name "-R0-RDSEL") (class "Default")
      (node (ref "IC1") (pin "1") (pinfunction "I0_1") (pintype "input"))
      (node (ref "IC1") (pin "4") (pinfunction "I0_4") (pintype "input"))
      (node (ref "IC2") (pin "1") (pinfunction "I0_1") (pintype "input"))
      (node (ref "IC2") (pin "4") (pinfunction "I0_4") (pintype "input"))
      (node (ref "IC33") (pin "4") (pinfunction "Y0_4") (pintype "output"))
    )
    (net (code "20") (name "-R1-ADDRSEL") (class "Default")
      (node (ref "IC17") (pin "1") (pinfunction "G_1") (pintype "input"))
      (node (ref "IC17") (pin "19") (pinfunction "G_19") (pintype "input"))
      (node (ref "IC18") (pin "1") (pinfunction "G_1") (pintype "input"))
      (node (ref "IC18") (pin "19") (pinfunction "G_19") (pintype "input"))
      (node (ref "IC38") (pin "5") (pinfunction "Y1_5") (pintype "output"))
    )
    (net (code "21") (name "-R1-LDSEL") (class "Default")
      (node (ref "IC15") (pin "12") (pinfunction "I0_12") (pintype "input"))
      (node (ref "IC15") (pin "9") (pinfunction "I0_9") (pintype "input"))
      (node (ref "IC33") (pin "11") (pinfunction "Y1_11") (pintype "output"))
    )
    (net (code "22") (name "-R1-RDSEL") (class "Default")
      (node (ref "IC15") (pin "1") (pinfunction "I0_1") (pintype "input"))
      (node (ref "IC15") (pin "4") (pinfunction "I0_4") (pintype "input"))
      (node (ref "IC2") (pin "12") (pinfunction "I0_12") (pintype "input"))
      (node (ref "IC2") (pin "9") (pinfunction "I0_9") (pintype "input"))
      (node (ref "IC33") (pin "5") (pinfunction "Y1_5") (pintype "output"))
    )
    (net (code "23") (name "-R2-ADDRSEL") (class "Default")
      (node (ref "IC27") (pin "1") (pinfunction "G_1") (pintype "input"))
      (node (ref "IC27") (pin "19") (pinfunction "G_19") (pintype "input"))
      (node (ref "IC28") (pin "1") (pinfunction "G_1") (pintype "input"))
      (node (ref "IC28") (pin "19") (pinfunction "G_19") (pintype "input"))
      (node (ref "IC38") (pin "6") (pinfunction "Y2_6") (pintype "output"))
    )
    (net (code "24") (name "-R2-LDSEL") (class "Default")
      (node (ref "IC25") (pin "12") (pinfunction "I0_12") (pintype "input"))
      (node (ref "IC25") (pin "9") (pinfunction "I0_9") (pintype "input"))
      (node (ref "IC33") (pin "10") (pinfunction "Y2_10") (pintype "output"))
    )
    (net (code "25") (name "-R2-RDSEL") (class "Default")
      (node (ref "IC25") (pin "1") (pinfunction "I0_1") (pintype "input"))
      (node (ref "IC25") (pin "4") (pinfunction "I0_4") (pintype "input"))
      (node (ref "IC26") (pin "1") (pinfunction "I0_1") (pintype "input"))
      (node (ref "IC26") (pin "4") (pinfunction "I0_4") (pintype "input"))
      (node (ref "IC33") (pin "6") (pinfunction "Y2_6") (pintype "output"))
    )
    (net (code "26") (name "-R3-ADDRSEL") (class "Default")
      (node (ref "IC38") (pin "7") (pinfunction "Y3_7") (pintype "output"))
      (node (ref "IC49") (pin "1") (pinfunction "G_1") (pintype "input"))
      (node (ref "IC49") (pin "19") (pinfunction "G_19") (pintype "input"))
      (node (ref "IC50") (pin "1") (pinfunction "G_1") (pintype "input"))
      (node (ref "IC50") (pin "19") (pinfunction "G_19") (pintype "input"))
    )
    (net (code "27") (name "-R3-LDSEL") (class "Default")
      (node (ref "IC33") (pin "9") (pinfunction "Y3_9") (pintype "output"))
      (node (ref "IC47") (pin "12") (pinfunction "I0_12") (pintype "input"))
      (node (ref "IC47") (pin "9") (pinfunction "I0_9") (pintype "input"))
    )
    (net (code "28") (name "-R3-RDSEL") (class "Default")
      (node (ref "IC26") (pin "12") (pinfunction "I0_12") (pintype "input"))
      (node (ref "IC26") (pin "9") (pinfunction "I0_9") (pintype "input"))
      (node (ref "IC33") (pin "7") (pinfunction "Y3_7") (pintype "output"))
      (node (ref "IC47") (pin "1") (pinfunction "I0_1") (pintype "input"))
      (node (ref "IC47") (pin "4") (pinfunction "I0_4") (pintype "input"))
    )
    (net (code "29") (name "-RDSEL") (class "Default")
      (node (ref "IC33") (pin "1") (pinfunction "G_1") (pintype "input"))
      (node (ref "IC34") (pin "12") (pinfunction "I0_12") (pintype "input"))
      (node (ref "J1") (pin "2") (pinfunction "2_2") (pintype "passive"))
      (node (ref "J1") (pin "4") (pinfunction "4_4") (pintype "passive"))
      (node (ref "J1") (pin "6") (pinfunction "6_6") (pintype "passive"))
      (node (ref "J1") (pin "8") (pinfunction "8_8") (pintype "passive"))
    )
    (net (code "30") (name "-REG-DN") (class "Default")
      (node (ref "IC1") (pin "5") (pinfunction "I1_5") (pintype "input"))
      (node (ref "IC15") (pin "5") (pinfunction "I1_5") (pintype "input"))
      (node (ref "IC25") (pin "5") (pinfunction "I1_5") (pintype "input"))
      (node (ref "IC47") (pin "5") (pinfunction "I1_5") (pintype "input"))
      (node (ref "X1") (pin "B21") (pinfunction "B_B21") (pintype "passive"))
    )
    (net (code "31") (name "-REG-FUNC-LD") (class "Default")
      (node (ref "IC31") (pin "5") (pinfunction "I1_5") (pintype "input"))
      (node (ref "X1") (pin "B8") (pinfunction "B_B8") (pintype "passive"))
    )
    (net (code "32") (name "-REG-FUNC-RD") (class "Default")
      (node (ref "IC31") (pin "2") (pinfunction "I1_2") (pintype "input"))
      (node (ref "X1") (pin "B7") (pinfunction "B_B7") (pintype "passive"))
    )
    (net (code "33") (name "-REG-LD-HI") (class "Default")
      (node (ref "IC1") (pin "13") (pinfunction "I1_13") (pintype "input"))
      (node (ref "IC15") (pin "13") (pinfunction "I1_13") (pintype "input"))
      (node (ref "IC25") (pin "13") (pinfunction "I1_13") (pintype "input"))
      (node (ref "IC47") (pin "13") (pinfunction "I1_13") (pintype "input"))
      (node (ref "X1") (pin "B20") (pinfunction "B_B20") (pintype "passive"))
    )
    (net (code "34") (name "-REG-LD-LO") (class "Default")
      (node (ref "IC1") (pin "10") (pinfunction "I1_10") (pintype "input"))
      (node (ref "IC15") (pin "10") (pinfunction "I1_10") (pintype "input"))
      (node (ref "IC25") (pin "10") (pinfunction "I1_10") (pintype "input"))
      (node (ref "IC47") (pin "10") (pinfunction "I1_10") (pintype "input"))
      (node (ref "X1") (pin "B18") (pinfunction "B_B18") (pintype "passive"))
    )
    (net (code "35") (name "-REG-RD-HI") (class "Default")
      (node (ref "IC2") (pin "13") (pinfunction "I1_13") (pintype "input"))
      (node (ref "IC2") (pin "5") (pinfunction "I1_5") (pintype "input"))
      (node (ref "IC26") (pin "13") (pinfunction "I1_13") (pintype "input"))
      (node (ref "IC26") (pin "5") (pinfunction "I1_5") (pintype "input"))
      (node (ref "X1") (pin "B19") (pinfunction "B_B19") (pintype "passive"))
    )
    (net (code "36") (name "-REG-RD-LO") (class "Default")
      (node (ref "IC2") (pin "10") (pinfunction "I1_10") (pintype "input"))
      (node (ref "IC2") (pin "2") (pinfunction "I1_2") (pintype "input"))
      (node (ref "IC26") (pin "10") (pinfunction "I1_10") (pintype "input"))
      (node (ref "IC26") (pin "2") (pinfunction "I1_2") (pintype "input"))
      (node (ref "X1") (pin "B17") (pinfunction "B_B17") (pintype "passive"))
    )
    (net (code "37") (name "-REG-UP") (class "Default")
      (node (ref "IC1") (pin "2") (pinfunction "I1_2") (pintype "input"))
      (node (ref "IC15") (pin "2") (pinfunction "I1_2") (pintype "input"))
      (node (ref "IC25") (pin "2") (pinfunction "I1_2") (pintype "input"))
      (node (ref "IC47") (pin "2") (pinfunction "I1_2") (pintype "input"))
      (node (ref "X1") (pin "B22") (pinfunction "B_B22") (pintype "passive"))
    )
    (net (code "38") (name "-RESET") (class "Default")
      (node (ref "IC34") (pin "2") (pinfunction "I1_2") (pintype "input"))
      (node (ref "X1") (pin "C30") (pinfunction "B_C30") (pintype "passive"))
    )
    (net (code "39") (name "-RLD0") (class "Default")
      (node (ref "IC32") (pin "12") (pinfunction "Y0_12") (pintype "output"))
      (node (ref "J2") (pin "1") (pinfunction "1_1") (pintype "passive"))
    )
    (net (code "40") (name "-RRD0") (class "Default")
      (node (ref "IC32") (pin "4") (pinfunction "Y0_4") (pintype "output"))
      (node (ref "J1") (pin "1") (pinfunction "1_1") (pintype "passive"))
    )
    (net (code "41") (name "-RUN") (class "Default")
      (node (ref "X1") (pin "C29") (pinfunction "B_C29") (pintype "passive"))
    )
    (net (code "42") (name "-SR-LD") (class "Default")
      (node (ref "X1") (pin "C23") (pinfunction "B_C23") (pintype "passive"))
    )
    (net (code "43") (name "-TMP-REG-LD0") (class "Default")
      (node (ref "X1") (pin "B28") (pinfunction "B_B28") (pintype "passive"))
    )
    (net (code "44") (name "-TMP-REG-LD1") (class "Default")
      (node (ref "X1") (pin "B30") (pinfunction "B_B30") (pintype "passive"))
    )
    (net (code "45") (name "-TMP-REG-RD0") (class "Default")
      (node (ref "X1") (pin "B27") (pinfunction "B_B27") (pintype "passive"))
    )
    (net (code "46") (name "-TMP-REG-RD1") (class "Default")
      (node (ref "X1") (pin "B29") (pinfunction "B_B29") (pintype "passive"))
    )
    (net (code "47") (name "-VMA") (class "Default")
      (node (ref "IC40") (pin "2") (pinfunction "I1_2") (pintype "input"))
      (node (ref "X1") (pin "C12") (pinfunction "B_C12") (pintype "passive"))
    )
    (net (code "48") (name "ADATA0") (class "Default")
      (node (ref "IC13") (pin "9") (pinfunction "Y1_9") (pintype "tri_state"))
      (node (ref "IC19") (pin "15") (pinfunction "A_15") (pintype "input"))
      (node (ref "IC23") (pin "9") (pinfunction "Y1_9") (pintype "tri_state"))
      (node (ref "IC29") (pin "15") (pinfunction "A_15") (pintype "input"))
      (node (ref "IC3") (pin "15") (pinfunction "A_15") (pintype "input"))
      (node (ref "IC35") (pin "18") (pinfunction "B1_18") (pintype "bidirectional"))
      (node (ref "IC45") (pin "9") (pinfunction "Y1_9") (pintype "tri_state"))
      (node (ref "IC7") (pin "9") (pinfunction "Y1_9") (pintype "tri_state"))
      (node (ref "IC9") (pin "15") (pinfunction "A_15") (pintype "input"))
      (node (ref "RN1") (pin "2") (pinfunction "1_2") (pintype "passive"))
    )
    (net (code "49") (name "ADATA1") (class "Default")
      (node (ref "IC13") (pin "7") (pinfunction "Y2_7") (pintype "tri_state"))
      (node (ref "IC19") (pin "1") (pinfunction "B_1") (pintype "input"))
      (node (ref "IC23") (pin "7") (pinfunction "Y2_7") (pintype "tri_state"))
      (node (ref "IC29") (pin "1") (pinfunction "B_1") (pintype "input"))
      (node (ref "IC3") (pin "1") (pinfunction "B_1") (pintype "input"))
      (node (ref "IC35") (pin "17") (pinfunction "B2_17") (pintype "bidirectional"))
      (node (ref "IC45") (pin "7") (pinfunction "Y2_7") (pintype "tri_state"))
      (node (ref "IC7") (pin "7") (pinfunction "Y2_7") (pintype "tri_state"))
      (node (ref "IC9") (pin "1") (pinfunction "B_1") (pintype "input"))
      (node (ref "RN1") (pin "3") (pinfunction "1_3") (pintype "passive"))
    )
    (net (code "50") (name "ADATA2") (class "Default")
      (node (ref "IC13") (pin "5") (pinfunction "Y3_5") (pintype "tri_state"))
      (node (ref "IC19") (pin "10") (pinfunction "C_10") (pintype "input"))
      (node (ref "IC23") (pin "5") (pinfunction "Y3_5") (pintype "tri_state"))
      (node (ref "IC29") (pin "10") (pinfunction "C_10") (pintype "input"))
      (node (ref "IC3") (pin "10") (pinfunction "C_10") (pintype "input"))
      (node (ref "IC35") (pin "16") (pinfunction "B3_16") (pintype "bidirectional"))
      (node (ref "IC45") (pin "5") (pinfunction "Y3_5") (pintype "tri_state"))
      (node (ref "IC7") (pin "5") (pinfunction "Y3_5") (pintype "tri_state"))
      (node (ref "IC9") (pin "10") (pinfunction "C_10") (pintype "input"))
      (node (ref "RN1") (pin "4") (pinfunction "1_4") (pintype "passive"))
    )
    (net (code "51") (name "ADATA3") (class "Default")
      (node (ref "IC13") (pin "3") (pinfunction "Y4_3") (pintype "tri_state"))
      (node (ref "IC19") (pin "9") (pinfunction "D_9") (pintype "input"))
      (node (ref "IC23") (pin "3") (pinfunction "Y4_3") (pintype "tri_state"))
      (node (ref "IC29") (pin "9") (pinfunction "D_9") (pintype "input"))
      (node (ref "IC3") (pin "9") (pinfunction "D_9") (pintype "input"))
      (node (ref "IC35") (pin "15") (pinfunction "B4_15") (pintype "bidirectional"))
      (node (ref "IC45") (pin "3") (pinfunction "Y4_3") (pintype "tri_state"))
      (node (ref "IC7") (pin "3") (pinfunction "Y4_3") (pintype "tri_state"))
      (node (ref "IC9") (pin "9") (pinfunction "D_9") (pintype "input"))
      (node (ref "RN1") (pin "5") (pinfunction "1_5") (pintype "passive"))
    )
    (net (code "52") (name "ADATA4") (class "Default")
      (node (ref "IC10") (pin "15") (pinfunction "A_15") (pintype "input"))
      (node (ref "IC13") (pin "18") (pinfunction "Y1_18") (pintype "tri_state"))
      (node (ref "IC20") (pin "15") (pinfunction "A_15") (pintype "input"))
      (node (ref "IC23") (pin "18") (pinfunction "Y1_18") (pintype "tri_state"))
      (node (ref "IC30") (pin "15") (pinfunction "A_15") (pintype "input"))
      (node (ref "IC35") (pin "14") (pinfunction "B5_14") (pintype "bidirectional"))
      (node (ref "IC4") (pin "15") (pinfunction "A_15") (pintype "input"))
      (node (ref "IC45") (pin "18") (pinfunction "Y1_18") (pintype "tri_state"))
      (node (ref "IC7") (pin "18") (pinfunction "Y1_18") (pintype "tri_state"))
      (node (ref "RN1") (pin "6") (pinfunction "1_6") (pintype "passive"))
    )
    (net (code "53") (name "ADATA5") (class "Default")
      (node (ref "IC10") (pin "1") (pinfunction "B_1") (pintype "input"))
      (node (ref "IC13") (pin "16") (pinfunction "Y2_16") (pintype "tri_state"))
      (node (ref "IC20") (pin "1") (pinfunction "B_1") (pintype "input"))
      (node (ref "IC23") (pin "16") (pinfunction "Y2_16") (pintype "tri_state"))
      (node (ref "IC30") (pin "1") (pinfunction "B_1") (pintype "input"))
      (node (ref "IC35") (pin "13") (pinfunction "B6_13") (pintype "bidirectional"))
      (node (ref "IC4") (pin "1") (pinfunction "B_1") (pintype "input"))
      (node (ref "IC45") (pin "16") (pinfunction "Y2_16") (pintype "tri_state"))
      (node (ref "IC7") (pin "16") (pinfunction "Y2_16") (pintype "tri_state"))
      (node (ref "RN1") (pin "7") (pinfunction "1_7") (pintype "passive"))
    )
    (net (code "54") (name "ADATA6") (class "Default")
      (node (ref "IC10") (pin "10") (pinfunction "C_10") (pintype "input"))
      (node (ref "IC13") (pin "14") (pinfunction "Y3_14") (pintype "tri_state"))
      (node (ref "IC20") (pin "10") (pinfunction "C_10") (pintype "input"))
      (node (ref "IC23") (pin "14") (pinfunction "Y3_14") (pintype "tri_state"))
      (node (ref "IC30") (pin "10") (pinfunction "C_10") (pintype "input"))
      (node (ref "IC35") (pin "12") (pinfunction "B7_12") (pintype "bidirectional"))
      (node (ref "IC4") (pin "10") (pinfunction "C_10") (pintype "input"))
      (node (ref "IC45") (pin "14") (pinfunction "Y3_14") (pintype "tri_state"))
      (node (ref "IC7") (pin "14") (pinfunction "Y3_14") (pintype "tri_state"))
      (node (ref "RN1") (pin "8") (pinfunction "1_8") (pintype "passive"))
    )
    (net (code "55") (name "ADATA7") (class "Default")
      (node (ref "IC10") (pin "9") (pinfunction "D_9") (pintype "input"))
      (node (ref "IC13") (pin "12") (pinfunction "Y4_12") (pintype "tri_state"))
      (node (ref "IC20") (pin "9") (pinfunction "D_9") (pintype "input"))
      (node (ref "IC23") (pin "12") (pinfunction "Y4_12") (pintype "tri_state"))
      (node (ref "IC30") (pin "9") (pinfunction "D_9") (pintype "input"))
      (node (ref "IC35") (pin "11") (pinfunction "B8_11") (pintype "bidirectional"))
      (node (ref "IC4") (pin "9") (pinfunction "D_9") (pintype "input"))
      (node (ref "IC45") (pin "12") (pinfunction "Y4_12") (pintype "tri_state"))
      (node (ref "IC7") (pin "12") (pinfunction "Y4_12") (pintype "tri_state"))
      (node (ref "RN1") (pin "9") (pinfunction "1_9") (pintype "passive"))
    )
    (net (code "56") (name "ADATA8") (class "Default")
      (node (ref "IC11") (pin "15") (pinfunction "A_15") (pintype "input"))
      (node (ref "IC14") (pin "9") (pinfunction "Y1_9") (pintype "tri_state"))
      (node (ref "IC21") (pin "15") (pinfunction "A_15") (pintype "input"))
      (node (ref "IC24") (pin "9") (pinfunction "Y1_9") (pintype "tri_state"))
      (node (ref "IC36") (pin "18") (pinfunction "B1_18") (pintype "bidirectional"))
      (node (ref "IC37") (pin "18") (pinfunction "B1_18") (pintype "bidirectional"))
      (node (ref "IC43") (pin "15") (pinfunction "A_15") (pintype "input"))
      (node (ref "IC46") (pin "9") (pinfunction "Y1_9") (pintype "tri_state"))
      (node (ref "IC5") (pin "15") (pinfunction "A_15") (pintype "input"))
      (node (ref "IC8") (pin "9") (pinfunction "Y1_9") (pintype "tri_state"))
      (node (ref "RN2") (pin "2") (pinfunction "1_2") (pintype "passive"))
    )
    (net (code "57") (name "ADATA9") (class "Default")
      (node (ref "IC11") (pin "1") (pinfunction "B_1") (pintype "input"))
      (node (ref "IC14") (pin "7") (pinfunction "Y2_7") (pintype "tri_state"))
      (node (ref "IC21") (pin "1") (pinfunction "B_1") (pintype "input"))
      (node (ref "IC24") (pin "7") (pinfunction "Y2_7") (pintype "tri_state"))
      (node (ref "IC36") (pin "17") (pinfunction "B2_17") (pintype "bidirectional"))
      (node (ref "IC37") (pin "17") (pinfunction "B2_17") (pintype "bidirectional"))
      (node (ref "IC43") (pin "1") (pinfunction "B_1") (pintype "input"))
      (node (ref "IC46") (pin "7") (pinfunction "Y2_7") (pintype "tri_state"))
      (node (ref "IC5") (pin "1") (pinfunction "B_1") (pintype "input"))
      (node (ref "IC8") (pin "7") (pinfunction "Y2_7") (pintype "tri_state"))
      (node (ref "RN2") (pin "3") (pinfunction "1_3") (pintype "passive"))
    )
    (net (code "58") (name "ADATA10") (class "Default")
      (node (ref "IC11") (pin "10") (pinfunction "C_10") (pintype "input"))
      (node (ref "IC14") (pin "5") (pinfunction "Y3_5") (pintype "tri_state"))
      (node (ref "IC21") (pin "10") (pinfunction "C_10") (pintype "input"))
      (node (ref "IC24") (pin "5") (pinfunction "Y3_5") (pintype "tri_state"))
      (node (ref "IC36") (pin "16") (pinfunction "B3_16") (pintype "bidirectional"))
      (node (ref "IC37") (pin "16") (pinfunction "B3_16") (pintype "bidirectional"))
      (node (ref "IC43") (pin "10") (pinfunction "C_10") (pintype "input"))
      (node (ref "IC46") (pin "5") (pinfunction "Y3_5") (pintype "tri_state"))
      (node (ref "IC5") (pin "10") (pinfunction "C_10") (pintype "input"))
      (node (ref "IC8") (pin "5") (pinfunction "Y3_5") (pintype "tri_state"))
      (node (ref "RN2") (pin "4") (pinfunction "1_4") (pintype "passive"))
    )
    (net (code "59") (name "ADATA11") (class "Default")
      (node (ref "IC11") (pin "9") (pinfunction "D_9") (pintype "input"))
      (node (ref "IC14") (pin "3") (pinfunction "Y4_3") (pintype "tri_state"))
      (node (ref "IC21") (pin "9") (pinfunction "D_9") (pintype "input"))
      (node (ref "IC24") (pin "3") (pinfunction "Y4_3") (pintype "tri_state"))
      (node (ref "IC36") (pin "15") (pinfunction "B4_15") (pintype "bidirectional"))
      (node (ref "IC37") (pin "15") (pinfunction "B4_15") (pintype "bidirectional"))
      (node (ref "IC43") (pin "9") (pinfunction "D_9") (pintype "input"))
      (node (ref "IC46") (pin "3") (pinfunction "Y4_3") (pintype "tri_state"))
      (node (ref "IC5") (pin "9") (pinfunction "D_9") (pintype "input"))
      (node (ref "IC8") (pin "3") (pinfunction "Y4_3") (pintype "tri_state"))
      (node (ref "RN2") (pin "5") (pinfunction "1_5") (pintype "passive"))
    )
    (net (code "60") (name "ADATA12") (class "Default")
      (node (ref "IC12") (pin "15") (pinfunction "A_15") (pintype "input"))
      (node (ref "IC14") (pin "18") (pinfunction "Y1_18") (pintype "tri_state"))
      (node (ref "IC22") (pin "15") (pinfunction "A_15") (pintype "input"))
      (node (ref "IC24") (pin "18") (pinfunction "Y1_18") (pintype "tri_state"))
      (node (ref "IC36") (pin "14") (pinfunction "B5_14") (pintype "bidirectional"))
      (node (ref "IC37") (pin "14") (pinfunction "B5_14") (pintype "bidirectional"))
      (node (ref "IC44") (pin "15") (pinfunction "A_15") (pintype "input"))
      (node (ref "IC46") (pin "18") (pinfunction "Y1_18") (pintype "tri_state"))
      (node (ref "IC6") (pin "15") (pinfunction "A_15") (pintype "input"))
      (node (ref "IC8") (pin "18") (pinfunction "Y1_18") (pintype "tri_state"))
      (node (ref "RN2") (pin "6") (pinfunction "1_6") (pintype "passive"))
    )
    (net (code "61") (name "ADATA13") (class "Default")
      (node (ref "IC12") (pin "1") (pinfunction "B_1") (pintype "input"))
      (node (ref "IC14") (pin "16") (pinfunction "Y2_16") (pintype "tri_state"))
      (node (ref "IC22") (pin "1") (pinfunction "B_1") (pintype "input"))
      (node (ref "IC24") (pin "16") (pinfunction "Y2_16") (pintype "tri_state"))
      (node (ref "IC36") (pin "13") (pinfunction "B6_13") (pintype "bidirectional"))
      (node (ref "IC37") (pin "13") (pinfunction "B6_13") (pintype "bidirectional"))
      (node (ref "IC44") (pin "1") (pinfunction "B_1") (pintype "input"))
      (node (ref "IC46") (pin "16") (pinfunction "Y2_16") (pintype "tri_state"))
      (node (ref "IC6") (pin "1") (pinfunction "B_1") (pintype "input"))
      (node (ref "IC8") (pin "16") (pinfunction "Y2_16") (pintype "tri_state"))
      (node (ref "RN2") (pin "7") (pinfunction "1_7") (pintype "passive"))
    )
    (net (code "62") (name "ADATA14") (class "Default")
      (node (ref "IC12") (pin "10") (pinfunction "C_10") (pintype "input"))
      (node (ref "IC14") (pin "14") (pinfunction "Y3_14") (pintype "tri_state"))
      (node (ref "IC22") (pin "10") (pinfunction "C_10") (pintype "input"))
      (node (ref "IC24") (pin "14") (pinfunction "Y3_14") (pintype "tri_state"))
      (node (ref "IC36") (pin "12") (pinfunction "B7_12") (pintype "bidirectional"))
      (node (ref "IC37") (pin "12") (pinfunction "B7_12") (pintype "bidirectional"))
      (node (ref "IC44") (pin "10") (pinfunction "C_10") (pintype "input"))
      (node (ref "IC46") (pin "14") (pinfunction "Y3_14") (pintype "tri_state"))
      (node (ref "IC6") (pin "10") (pinfunction "C_10") (pintype "input"))
      (node (ref "IC8") (pin "14") (pinfunction "Y3_14") (pintype "tri_state"))
      (node (ref "RN2") (pin "8") (pinfunction "1_8") (pintype "passive"))
    )
    (net (code "63") (name "ADATA15") (class "Default")
      (node (ref "IC12") (pin "9") (pinfunction "D_9") (pintype "input"))
      (node (ref "IC14") (pin "12") (pinfunction "Y4_12") (pintype "tri_state"))
      (node (ref "IC22") (pin "9") (pinfunction "D_9") (pintype "input"))
      (node (ref "IC24") (pin "12") (pinfunction "Y4_12") (pintype "tri_state"))
      (node (ref "IC36") (pin "11") (pinfunction "B8_11") (pintype "bidirectional"))
      (node (ref "IC37") (pin "11") (pinfunction "B8_11") (pintype "bidirectional"))
      (node (ref "IC44") (pin "9") (pinfunction "D_9") (pintype "input"))
      (node (ref "IC46") (pin "12") (pinfunction "Y4_12") (pintype "tri_state"))
      (node (ref "IC6") (pin "9") (pinfunction "D_9") (pintype "input"))
      (node (ref "IC8") (pin "12") (pinfunction "Y4_12") (pintype "tri_state"))
      (node (ref "RN2") (pin "9") (pinfunction "1_9") (pintype "passive"))
    )
    (net (code "64") (name "ADDR-REG-ID0") (class "Default")
      (node (ref "IC38") (pin "2") (pinfunction "A_2") (pintype "input"))
      (node (ref "X1") (pin "C3") (pinfunction "B_C3") (pintype "passive"))
    )
    (net (code "65") (name "ADDR-REG-ID1") (class "Default")
      (node (ref "IC38") (pin "3") (pinfunction "B_3") (pintype "input"))
      (node (ref "X1") (pin "C4") (pinfunction "B_C4") (pintype "passive"))
    )
    (net (code "66") (name "ADDR-REG-ID2") (class "Default")
      (node (ref "IC38") (pin "14") (pinfunction "A_14") (pintype "input"))
      (node (ref "X1") (pin "C5") (pinfunction "B_C5") (pintype "passive"))
    )
    (net (code "67") (name "ADDR-REG-ID3") (class "Default")
      (node (ref "IC38") (pin "13") (pinfunction "B_13") (pintype "input"))
      (node (ref "X1") (pin "C6") (pinfunction "B_C6") (pintype "passive"))
    )
    (net (code "68") (name "ADDR0") (class "Default")
      (node (ref "IC17") (pin "18") (pinfunction "Y1_18") (pintype "tri_state"))
      (node (ref "IC27") (pin "18") (pinfunction "Y1_18") (pintype "tri_state"))
      (node (ref "IC41") (pin "18") (pinfunction "Y1_18") (pintype "tri_state"))
      (node (ref "IC49") (pin "18") (pinfunction "Y1_18") (pintype "tri_state"))
      (node (ref "X1") (pin "A3") (pinfunction "B_A3") (pintype "passive"))
    )
    (net (code "69") (name "ADDR1") (class "Default")
      (node (ref "IC17") (pin "16") (pinfunction "Y2_16") (pintype "tri_state"))
      (node (ref "IC27") (pin "16") (pinfunction "Y2_16") (pintype "tri_state"))
      (node (ref "IC41") (pin "16") (pinfunction "Y2_16") (pintype "tri_state"))
      (node (ref "IC49") (pin "16") (pinfunction "Y2_16") (pintype "tri_state"))
      (node (ref "X1") (pin "A4") (pinfunction "B_A4") (pintype "passive"))
    )
    (net (code "70") (name "ADDR2") (class "Default")
      (node (ref "IC17") (pin "14") (pinfunction "Y3_14") (pintype "tri_state"))
      (node (ref "IC27") (pin "14") (pinfunction "Y3_14") (pintype "tri_state"))
      (node (ref "IC41") (pin "14") (pinfunction "Y3_14") (pintype "tri_state"))
      (node (ref "IC49") (pin "14") (pinfunction "Y3_14") (pintype "tri_state"))
      (node (ref "X1") (pin "A5") (pinfunction "B_A5") (pintype "passive"))
    )
    (net (code "71") (name "ADDR3") (class "Default")
      (node (ref "IC17") (pin "12") (pinfunction "Y4_12") (pintype "tri_state"))
      (node (ref "IC27") (pin "12") (pinfunction "Y4_12") (pintype "tri_state"))
      (node (ref "IC41") (pin "12") (pinfunction "Y4_12") (pintype "tri_state"))
      (node (ref "IC49") (pin "12") (pinfunction "Y4_12") (pintype "tri_state"))
      (node (ref "X1") (pin "A6") (pinfunction "B_A6") (pintype "passive"))
    )
    (net (code "72") (name "ADDR4") (class "Default")
      (node (ref "IC17") (pin "9") (pinfunction "Y1_9") (pintype "tri_state"))
      (node (ref "IC27") (pin "9") (pinfunction "Y1_9") (pintype "tri_state"))
      (node (ref "IC41") (pin "9") (pinfunction "Y1_9") (pintype "tri_state"))
      (node (ref "IC49") (pin "9") (pinfunction "Y1_9") (pintype "tri_state"))
      (node (ref "X1") (pin "A7") (pinfunction "B_A7") (pintype "passive"))
    )
    (net (code "73") (name "ADDR5") (class "Default")
      (node (ref "IC17") (pin "7") (pinfunction "Y2_7") (pintype "tri_state"))
      (node (ref "IC27") (pin "7") (pinfunction "Y2_7") (pintype "tri_state"))
      (node (ref "IC41") (pin "7") (pinfunction "Y2_7") (pintype "tri_state"))
      (node (ref "IC49") (pin "7") (pinfunction "Y2_7") (pintype "tri_state"))
      (node (ref "X1") (pin "A8") (pinfunction "B_A8") (pintype "passive"))
    )
    (net (code "74") (name "ADDR6") (class "Default")
      (node (ref "IC17") (pin "5") (pinfunction "Y3_5") (pintype "tri_state"))
      (node (ref "IC27") (pin "5") (pinfunction "Y3_5") (pintype "tri_state"))
      (node (ref "IC41") (pin "5") (pinfunction "Y3_5") (pintype "tri_state"))
      (node (ref "IC49") (pin "5") (pinfunction "Y3_5") (pintype "tri_state"))
      (node (ref "X1") (pin "A9") (pinfunction "B_A9") (pintype "passive"))
    )
    (net (code "75") (name "ADDR7") (class "Default")
      (node (ref "IC17") (pin "3") (pinfunction "Y4_3") (pintype "tri_state"))
      (node (ref "IC27") (pin "3") (pinfunction "Y4_3") (pintype "tri_state"))
      (node (ref "IC41") (pin "3") (pinfunction "Y4_3") (pintype "tri_state"))
      (node (ref "IC49") (pin "3") (pinfunction "Y4_3") (pintype "tri_state"))
      (node (ref "X1") (pin "A10") (pinfunction "B_A10") (pintype "passive"))
    )
    (net (code "76") (name "ADDR8") (class "Default")
      (node (ref "IC18") (pin "18") (pinfunction "Y1_18") (pintype "tri_state"))
      (node (ref "IC28") (pin "18") (pinfunction "Y1_18") (pintype "tri_state"))
      (node (ref "IC42") (pin "18") (pinfunction "Y1_18") (pintype "tri_state"))
      (node (ref "IC50") (pin "18") (pinfunction "Y1_18") (pintype "tri_state"))
      (node (ref "X1") (pin "A11") (pinfunction "B_A11") (pintype "passive"))
    )
    (net (code "77") (name "ADDR9") (class "Default")
      (node (ref "IC18") (pin "16") (pinfunction "Y2_16") (pintype "tri_state"))
      (node (ref "IC28") (pin "16") (pinfunction "Y2_16") (pintype "tri_state"))
      (node (ref "IC42") (pin "16") (pinfunction "Y2_16") (pintype "tri_state"))
      (node (ref "IC50") (pin "16") (pinfunction "Y2_16") (pintype "tri_state"))
      (node (ref "X1") (pin "A12") (pinfunction "B_A12") (pintype "passive"))
    )
    (net (code "78") (name "ADDR10") (class "Default")
      (node (ref "IC18") (pin "14") (pinfunction "Y3_14") (pintype "tri_state"))
      (node (ref "IC28") (pin "14") (pinfunction "Y3_14") (pintype "tri_state"))
      (node (ref "IC42") (pin "14") (pinfunction "Y3_14") (pintype "tri_state"))
      (node (ref "IC50") (pin "14") (pinfunction "Y3_14") (pintype "tri_state"))
      (node (ref "X1") (pin "A13") (pinfunction "B_A13") (pintype "passive"))
    )
    (net (code "79") (name "ADDR11") (class "Default")
      (node (ref "IC18") (pin "12") (pinfunction "Y4_12") (pintype "tri_state"))
      (node (ref "IC28") (pin "12") (pinfunction "Y4_12") (pintype "tri_state"))
      (node (ref "IC42") (pin "12") (pinfunction "Y4_12") (pintype "tri_state"))
      (node (ref "IC50") (pin "12") (pinfunction "Y4_12") (pintype "tri_state"))
      (node (ref "X1") (pin "A14") (pinfunction "B_A14") (pintype "passive"))
    )
    (net (code "80") (name "ADDR12") (class "Default")
      (node (ref "IC18") (pin "9") (pinfunction "Y1_9") (pintype "tri_state"))
      (node (ref "IC28") (pin "9") (pinfunction "Y1_9") (pintype "tri_state"))
      (node (ref "IC42") (pin "9") (pinfunction "Y1_9") (pintype "tri_state"))
      (node (ref "IC50") (pin "9") (pinfunction "Y1_9") (pintype "tri_state"))
      (node (ref "X1") (pin "A15") (pinfunction "B_A15") (pintype "passive"))
    )
    (net (code "81") (name "ADDR13") (class "Default")
      (node (ref "IC18") (pin "7") (pinfunction "Y2_7") (pintype "tri_state"))
      (node (ref "IC28") (pin "7") (pinfunction "Y2_7") (pintype "tri_state"))
      (node (ref "IC42") (pin "7") (pinfunction "Y2_7") (pintype "tri_state"))
      (node (ref "IC50") (pin "7") (pinfunction "Y2_7") (pintype "tri_state"))
      (node (ref "X1") (pin "A16") (pinfunction "B_A16") (pintype "passive"))
    )
    (net (code "82") (name "ADDR14") (class "Default")
      (node (ref "IC18") (pin "5") (pinfunction "Y3_5") (pintype "tri_state"))
      (node (ref "IC28") (pin "5") (pinfunction "Y3_5") (pintype "tri_state"))
      (node (ref "IC42") (pin "5") (pinfunction "Y3_5") (pintype "tri_state"))
      (node (ref "IC50") (pin "5") (pinfunction "Y3_5") (pintype "tri_state"))
      (node (ref "X1") (pin "A17") (pinfunction "B_A17") (pintype "passive"))
    )
    (net (code "83") (name "ADDR15") (class "Default")
      (node (ref "IC18") (pin "3") (pinfunction "Y4_3") (pintype "tri_state"))
      (node (ref "IC28") (pin "3") (pinfunction "Y4_3") (pintype "tri_state"))
      (node (ref "IC42") (pin "3") (pinfunction "Y4_3") (pintype "tri_state"))
      (node (ref "IC50") (pin "3") (pinfunction "Y4_3") (pintype "tri_state"))
      (node (ref "X1") (pin "A18") (pinfunction "B_A18") (pintype "passive"))
    )
    (net (code "84") (name "ALU0") (class "Default")
      (node (ref "X1") (pin "C16") (pinfunction "B_C16") (pintype "passive"))
    )
    (net (code "85") (name "ALU1") (class "Default")
      (node (ref "X1") (pin "C17") (pinfunction "B_C17") (pintype "passive"))
    )
    (net (code "86") (name "ALU2") (class "Default")
      (node (ref "X1") (pin "C18") (pinfunction "B_C18") (pintype "passive"))
    )
    (net (code "87") (name "ALU3") (class "Default")
      (node (ref "X1") (pin "C19") (pinfunction "B_C19") (pintype "passive"))
    )
    (net (code "88") (name "BR-COND") (class "Default")
      (node (ref "X1") (pin "C24") (pinfunction "B_C24") (pintype "passive"))
    )
    (net (code "89") (name "BUS-DIR") (class "Default")
      (node (ref "IC34") (pin "4") (pinfunction "O_4") (pintype "output"))
      (node (ref "IC35") (pin "1") (pinfunction "DIR_1") (pintype "input"))
      (node (ref "IC36") (pin "1") (pinfunction "DIR_1") (pintype "input"))
      (node (ref "IC37") (pin "1") (pinfunction "DIR_1") (pintype "input"))
    )
    (net (code "90") (name "DATA0") (class "Default")
      (node (ref "IC35") (pin "2") (pinfunction "A1_2") (pintype "bidirectional"))
      (node (ref "IC37") (pin "2") (pinfunction "A1_2") (pintype "bidirectional"))
      (node (ref "X1") (pin "A19") (pinfunction "B_A19") (pintype "passive"))
    )
    (net (code "91") (name "DATA1") (class "Default")
      (node (ref "IC35") (pin "3") (pinfunction "A2_3") (pintype "bidirectional"))
      (node (ref "IC37") (pin "3") (pinfunction "A2_3") (pintype "bidirectional"))
      (node (ref "X1") (pin "A20") (pinfunction "B_A20") (pintype "passive"))
    )
    (net (code "92") (name "DATA2") (class "Default")
      (node (ref "IC35") (pin "4") (pinfunction "A3_4") (pintype "bidirectional"))
      (node (ref "IC37") (pin "4") (pinfunction "A3_4") (pintype "bidirectional"))
      (node (ref "X1") (pin "A21") (pinfunction "B_A21") (pintype "passive"))
    )
    (net (code "93") (name "DATA3") (class "Default")
      (node (ref "IC35") (pin "5") (pinfunction "A4_5") (pintype "bidirectional"))
      (node (ref "IC37") (pin "5") (pinfunction "A4_5") (pintype "bidirectional"))
      (node (ref "X1") (pin "A22") (pinfunction "B_A22") (pintype "passive"))
    )
    (net (code "94") (name "DATA4") (class "Default")
      (node (ref "IC35") (pin "6") (pinfunction "A5_6") (pintype "bidirectional"))
      (node (ref "IC37") (pin "6") (pinfunction "A5_6") (pintype "bidirectional"))
      (node (ref "X1") (pin "A23") (pinfunction "B_A23") (pintype "passive"))
    )
    (net (code "95") (name "DATA5") (class "Default")
      (node (ref "IC35") (pin "7") (pinfunction "A6_7") (pintype "bidirectional"))
      (node (ref "IC37") (pin "7") (pinfunction "A6_7") (pintype "bidirectional"))
      (node (ref "X1") (pin "A24") (pinfunction "B_A24") (pintype "passive"))
    )
    (net (code "96") (name "DATA6") (class "Default")
      (node (ref "IC35") (pin "8") (pinfunction "A7_8") (pintype "bidirectional"))
      (node (ref "IC37") (pin "8") (pinfunction "A7_8") (pintype "bidirectional"))
      (node (ref "X1") (pin "A25") (pinfunction "B_A25") (pintype "passive"))
    )
    (net (code "97") (name "DATA7") (class "Default")
      (node (ref "IC35") (pin "9") (pinfunction "A8_9") (pintype "bidirectional"))
      (node (ref "IC37") (pin "9") (pinfunction "A8_9") (pintype "bidirectional"))
      (node (ref "X1") (pin "A26") (pinfunction "B_A26") (pintype "passive"))
    )
    (net (code "98") (name "DATA8") (class "Default")
      (node (ref "IC36") (pin "2") (pinfunction "A1_2") (pintype "bidirectional"))
      (node (ref "X1") (pin "A27") (pinfunction "B_A27") (pintype "passive"))
    )
    (net (code "99") (name "DATA9") (class "Default")
      (node (ref "IC36") (pin "3") (pinfunction "A2_3") (pintype "bidirectional"))
      (node (ref "X1") (pin "A28") (pinfunction "B_A28") (pintype "passive"))
    )
    (net (code "100") (name "DATA10") (class "Default")
      (node (ref "IC36") (pin "4") (pinfunction "A3_4") (pintype "bidirectional"))
      (node (ref "X1") (pin "A29") (pinfunction "B_A29") (pintype "passive"))
    )
    (net (code "101") (name "DATA11") (class "Default")
      (node (ref "IC36") (pin "5") (pinfunction "A4_5") (pintype "bidirectional"))
      (node (ref "X1") (pin "A30") (pinfunction "B_A30") (pintype "passive"))
    )
    (net (code "102") (name "DATA12") (class "Default")
      (node (ref "IC36") (pin "6") (pinfunction "A5_6") (pintype "bidirectional"))
      (node (ref "X1") (pin "B3") (pinfunction "B_B3") (pintype "passive"))
    )
    (net (code "103") (name "DATA13") (class "Default")
      (node (ref "IC36") (pin "7") (pinfunction "A6_7") (pintype "bidirectional"))
      (node (ref "X1") (pin "B4") (pinfunction "B_B4") (pintype "passive"))
    )
    (net (code "104") (name "DATA14") (class "Default")
      (node (ref "IC36") (pin "8") (pinfunction "A7_8") (pintype "bidirectional"))
      (node (ref "X1") (pin "B5") (pinfunction "B_B5") (pintype "passive"))
    )
    (net (code "105") (name "DATA15") (class "Default")
      (node (ref "IC36") (pin "9") (pinfunction "A8_9") (pintype "bidirectional"))
      (node (ref "X1") (pin "B6") (pinfunction "B_B6") (pintype "passive"))
    )
    (net (code "106") (name "GND") (class "Default")
      (node (ref "C1") (pin "2") (pinfunction "2_2") (pintype "passive"))
      (node (ref "C10") (pin "2") (pinfunction "2_2") (pintype "passive"))
      (node (ref "C11") (pin "2") (pinfunction "2_2") (pintype "passive"))
      (node (ref "C12") (pin "2") (pinfunction "2_2") (pintype "passive"))
      (node (ref "C13") (pin "2") (pinfunction "2_2") (pintype "passive"))
      (node (ref "C14") (pin "2") (pinfunction "2_2") (pintype "passive"))
      (node (ref "C15") (pin "2") (pinfunction "2_2") (pintype "passive"))
      (node (ref "C16") (pin "2") (pinfunction "2_2") (pintype "passive"))
      (node (ref "C17") (pin "2") (pinfunction "2_2") (pintype "passive"))
      (node (ref "C18") (pin "2") (pinfunction "2_2") (pintype "passive"))
      (node (ref "C19") (pin "2") (pinfunction "2_2") (pintype "passive"))
      (node (ref "C2") (pin "2") (pinfunction "2_2") (pintype "passive"))
      (node (ref "C20") (pin "2") (pinfunction "2_2") (pintype "passive"))
      (node (ref "C21") (pin "2") (pinfunction "2_2") (pintype "passive"))
      (node (ref "C22") (pin "2") (pinfunction "2_2") (pintype "passive"))
      (node (ref "C23") (pin "2") (pinfunction "2_2") (pintype "passive"))
      (node (ref "C24") (pin "2") (pinfunction "2_2") (pintype "passive"))
      (node (ref "C25") (pin "2") (pinfunction "2_2") (pintype "passive"))
      (node (ref "C26") (pin "2") (pinfunction "2_2") (pintype "passive"))
      (node (ref "C27") (pin "2") (pinfunction "2_2") (pintype "passive"))
      (node (ref "C28") (pin "2") (pinfunction "2_2") (pintype "passive"))
      (node (ref "C29") (pin "2") (pinfunction "2_2") (pintype "passive"))
      (node (ref "C3") (pin "2") (pinfunction "2_2") (pintype "passive"))
      (node (ref "C30") (pin "2") (pinfunction "2_2") (pintype "passive"))
      (node (ref "C31") (pin "2") (pinfunction "2_2") (pintype "passive"))
      (node (ref "C32") (pin "2") (pinfunction "2_2") (pintype "passive"))
      (node (ref "C33") (pin "2") (pinfunction "2_2") (pintype "passive"))
      (node (ref "C34") (pin "2") (pinfunction "2_2") (pintype "passive"))
      (node (ref "C35") (pin "2") (pinfunction "2_2") (pintype "passive"))
      (node (ref "C36") (pin "2") (pinfunction "2_2") (pintype "passive"))
      (node (ref "C37") (pin "2") (pinfunction "2_2") (pintype "passive"))
      (node (ref "C38") (pin "2") (pinfunction "2_2") (pintype "passive"))
      (node (ref "C39") (pin "2") (pinfunction "2_2") (pintype "passive"))
      (node (ref "C4") (pin "2") (pinfunction "2_2") (pintype "passive"))
      (node (ref "C40") (pin "2") (pinfunction "2_2") (pintype "passive"))
      (node (ref "C41") (pin "2") (pinfunction "2_2") (pintype "passive"))
      (node (ref "C42") (pin "2") (pinfunction "2_2") (pintype "passive"))
      (node (ref "C43") (pin "2") (pinfunction "2_2") (pintype "passive"))
      (node (ref "C44") (pin "2") (pinfunction "2_2") (pintype "passive"))
      (node (ref "C45") (pin "2") (pinfunction "2_2") (pintype "passive"))
      (node (ref "C46") (pin "2") (pinfunction "2_2") (pintype "passive"))
      (node (ref "C47") (pin "2") (pinfunction "2_2") (pintype "passive"))
      (node (ref "C5") (pin "2") (pinfunction "2_2") (pintype "passive"))
      (node (ref "C6") (pin "2") (pinfunction "2_2") (pintype "passive"))
      (node (ref "C7") (pin "2") (pinfunction "2_2") (pintype "passive"))
      (node (ref "C8") (pin "2") (pinfunction "2_2") (pintype "passive"))
      (node (ref "C9") (pin "2") (pinfunction "2_2") (pintype "passive"))
      (node (ref "IC34") (pin "1") (pinfunction "I0_1") (pintype "input"))
      (node (ref "IC34") (pin "5") (pinfunction "I0_5") (pintype "input"))
      (node (ref "IC34") (pin "7") (pinfunction "VSS_7") (pintype "power_in"))
      (node (ref "IC34") (pin "8") (pinfunction "I0_8") (pintype "input"))
      (node (ref "IC40") (pin "10") (pinfunction "I1_10") (pintype "input"))
      (node (ref "IC40") (pin "12") (pinfunction "I0_12") (pintype "input"))
      (node (ref "IC40") (pin "13") (pinfunction "I1_13") (pintype "input"))
      (node (ref "IC40") (pin "4") (pinfunction "I0_4") (pintype "input"))
      (node (ref "IC40") (pin "5") (pinfunction "I1_5") (pintype "input"))
      (node (ref "IC40") (pin "9") (pinfunction "I0_9") (pintype "input"))
      (node (ref "PWR") (pin "K") (pinfunction "C_K") (pintype "passive"))
      (node (ref "X1") (pin "A1") (pinfunction "B_A1") (pintype "passive"))
      (node (ref "X1") (pin "A32") (pinfunction "B_A32") (pintype "passive"))
      (node (ref "X1") (pin "B1") (pinfunction "B_B1") (pintype "passive"))
      (node (ref "X1") (pin "B32") (pinfunction "B_B32") (pintype "passive"))
      (node (ref "X1") (pin "C1") (pinfunction "B_C1") (pintype "passive"))
      (node (ref "X1") (pin "C32") (pinfunction "B_C32") (pintype "passive"))
    )
    (net (code "107") (name "IN") (class "Default")
      (node (ref "X1") (pin "C26") (pinfunction "B_C26") (pintype "passive"))
    )
    (net (code "108") (name "IOADDR0") (class "Default")
      (node (ref "X1") (pin "C7") (pinfunction "B_C7") (pintype "passive"))
    )
    (net (code "109") (name "IOADDR1") (class "Default")
      (node (ref "X1") (pin "C8") (pinfunction "B_C8") (pintype "passive"))
    )
    (net (code "110") (name "IOADDR2") (class "Default")
      (node (ref "X1") (pin "C9") (pinfunction "B_C9") (pintype "passive"))
    )
    (net (code "111") (name "IOADDR3") (class "Default")
      (node (ref "X1") (pin "C10") (pinfunction "B_C10") (pintype "passive"))
    )
    (net (code "112") (name "Net-(IC1A-O)") (class "Default")
      (node (ref "IC1") (pin "3") (pinfunction "O_3") (pintype "output"))
      (node (ref "IC3") (pin "5") (pinfunction "UP_5") (pintype "input"))
    )
    (net (code "113") (name "Net-(IC1B-O)") (class "Default")
      (node (ref "IC1") (pin "6") (pinfunction "O_6") (pintype "output"))
      (node (ref "IC3") (pin "4") (pinfunction "DN_4") (pintype "input"))
    )
    (net (code "114") (name "Net-(IC1C-O)") (class "Default")
      (node (ref "IC1") (pin "8") (pinfunction "O_8") (pintype "output"))
      (node (ref "IC3") (pin "11") (pinfunction "LD_11") (pintype "input"))
      (node (ref "IC4") (pin "11") (pinfunction "LD_11") (pintype "input"))
    )
    (net (code "115") (name "Net-(IC1D-O)") (class "Default")
      (node (ref "IC1") (pin "11") (pinfunction "O_11") (pintype "output"))
      (node (ref "IC5") (pin "11") (pinfunction "LD_11") (pintype "input"))
      (node (ref "IC6") (pin "11") (pinfunction "LD_11") (pintype "input"))
    )
    (net (code "116") (name "Net-(IC2A-O)") (class "Default")
      (node (ref "IC2") (pin "3") (pinfunction "O_3") (pintype "output"))
      (node (ref "IC7") (pin "1") (pinfunction "G_1") (pintype "input"))
      (node (ref "IC7") (pin "19") (pinfunction "G_19") (pintype "input"))
    )
    (net (code "117") (name "Net-(IC2B-O)") (class "Default")
      (node (ref "IC2") (pin "6") (pinfunction "O_6") (pintype "output"))
      (node (ref "IC8") (pin "1") (pinfunction "G_1") (pintype "input"))
      (node (ref "IC8") (pin "19") (pinfunction "G_19") (pintype "input"))
    )
    (net (code "118") (name "Net-(IC3A-BO)") (class "Default")
      (node (ref "IC3") (pin "13") (pinfunction "BO_13") (pintype "output"))
      (node (ref "IC4") (pin "4") (pinfunction "DN_4") (pintype "input"))
    )
    (net (code "119") (name "Net-(IC3A-CO)") (class "Default")
      (node (ref "IC3") (pin "12") (pinfunction "CO_12") (pintype "output"))
      (node (ref "IC4") (pin "5") (pinfunction "UP_5") (pintype "input"))
    )
    (net (code "120") (name "Net-(IC3A-QA)") (class "Default")
      (node (ref "IC3") (pin "3") (pinfunction "QA_3") (pintype "output"))
      (node (ref "IC41") (pin "2") (pinfunction "A1_2") (pintype "input"))
      (node (ref "IC7") (pin "11") (pinfunction "A1_11") (pintype "input"))
    )
    (net (code "121") (name "Net-(IC3A-QB)") (class "Default")
      (node (ref "IC3") (pin "2") (pinfunction "QB_2") (pintype "output"))
      (node (ref "IC41") (pin "4") (pinfunction "A2_4") (pintype "input"))
      (node (ref "IC7") (pin "13") (pinfunction "A2_13") (pintype "input"))
    )
    (net (code "122") (name "Net-(IC3A-QC)") (class "Default")
      (node (ref "IC3") (pin "6") (pinfunction "QC_6") (pintype "output"))
      (node (ref "IC41") (pin "6") (pinfunction "A3_6") (pintype "input"))
      (node (ref "IC7") (pin "15") (pinfunction "A3_15") (pintype "input"))
    )
    (net (code "123") (name "Net-(IC3A-QD)") (class "Default")
      (node (ref "IC3") (pin "7") (pinfunction "QD_7") (pintype "output"))
      (node (ref "IC41") (pin "8") (pinfunction "A4_8") (pintype "input"))
      (node (ref "IC7") (pin "17") (pinfunction "A4_17") (pintype "input"))
    )
    (net (code "124") (name "Net-(IC4A-BO)") (class "Default")
      (node (ref "IC4") (pin "13") (pinfunction "BO_13") (pintype "output"))
      (node (ref "IC5") (pin "4") (pinfunction "DN_4") (pintype "input"))
    )
    (net (code "125") (name "Net-(IC4A-CO)") (class "Default")
      (node (ref "IC4") (pin "12") (pinfunction "CO_12") (pintype "output"))
      (node (ref "IC5") (pin "5") (pinfunction "UP_5") (pintype "input"))
    )
    (net (code "126") (name "Net-(IC5A-BO)") (class "Default")
      (node (ref "IC5") (pin "13") (pinfunction "BO_13") (pintype "output"))
      (node (ref "IC6") (pin "4") (pinfunction "DN_4") (pintype "input"))
    )
    (net (code "127") (name "Net-(IC5A-CO)") (class "Default")
      (node (ref "IC5") (pin "12") (pinfunction "CO_12") (pintype "output"))
      (node (ref "IC6") (pin "5") (pinfunction "UP_5") (pintype "input"))
    )
    (net (code "128") (name "Net-(IC10A-BO)") (class "Default")
      (node (ref "IC10") (pin "13") (pinfunction "BO_13") (pintype "output"))
      (node (ref "IC11") (pin "4") (pinfunction "DN_4") (pintype "input"))
    )
    (net (code "129") (name "Net-(IC10A-CO)") (class "Default")
      (node (ref "IC10") (pin "12") (pinfunction "CO_12") (pintype "output"))
      (node (ref "IC11") (pin "5") (pinfunction "UP_5") (pintype "input"))
    )
    (net (code "130") (name "Net-(IC10A-DN)") (class "Default")
      (node (ref "IC10") (pin "4") (pinfunction "DN_4") (pintype "input"))
      (node (ref "IC9") (pin "13") (pinfunction "BO_13") (pintype "output"))
    )
    (net (code "131") (name "Net-(IC10A-LD)") (class "Default")
      (node (ref "IC10") (pin "11") (pinfunction "LD_11") (pintype "input"))
      (node (ref "IC15") (pin "8") (pinfunction "O_8") (pintype "output"))
      (node (ref "IC9") (pin "11") (pinfunction "LD_11") (pintype "input"))
    )
    (net (code "132") (name "Net-(IC10A-QA)") (class "Default")
      (node (ref "IC10") (pin "3") (pinfunction "QA_3") (pintype "output"))
      (node (ref "IC13") (pin "2") (pinfunction "A1_2") (pintype "input"))
      (node (ref "IC17") (pin "11") (pinfunction "A1_11") (pintype "input"))
    )
    (net (code "133") (name "Net-(IC10A-QB)") (class "Default")
      (node (ref "IC10") (pin "2") (pinfunction "QB_2") (pintype "output"))
      (node (ref "IC13") (pin "4") (pinfunction "A2_4") (pintype "input"))
      (node (ref "IC17") (pin "13") (pinfunction "A2_13") (pintype "input"))
    )
    (net (code "134") (name "Net-(IC10A-QC)") (class "Default")
      (node (ref "IC10") (pin "6") (pinfunction "QC_6") (pintype "output"))
      (node (ref "IC13") (pin "6") (pinfunction "A3_6") (pintype "input"))
      (node (ref "IC17") (pin "15") (pinfunction "A3_15") (pintype "input"))
    )
    (net (code "135") (name "Net-(IC10A-QD)") (class "Default")
      (node (ref "IC10") (pin "7") (pinfunction "QD_7") (pintype "output"))
      (node (ref "IC13") (pin "8") (pinfunction "A4_8") (pintype "input"))
      (node (ref "IC17") (pin "17") (pinfunction "A4_17") (pintype "input"))
    )
    (net (code "136") (name "Net-(IC10A-UP)") (class "Default")
      (node (ref "IC10") (pin "5") (pinfunction "UP_5") (pintype "input"))
      (node (ref "IC9") (pin "12") (pinfunction "CO_12") (pintype "output"))
    )
    (net (code "137") (name "Net-(IC11A-BO)") (class "Default")
      (node (ref "IC11") (pin "13") (pinfunction "BO_13") (pintype "output"))
      (node (ref "IC12") (pin "4") (pinfunction "DN_4") (pintype "input"))
    )
    (net (code "138") (name "Net-(IC11A-CO)") (class "Default")
      (node (ref "IC11") (pin "12") (pinfunction "CO_12") (pintype "output"))
      (node (ref "IC12") (pin "5") (pinfunction "UP_5") (pintype "input"))
    )
    (net (code "139") (name "Net-(IC11A-LD)") (class "Default")
      (node (ref "IC11") (pin "11") (pinfunction "LD_11") (pintype "input"))
      (node (ref "IC12") (pin "11") (pinfunction "LD_11") (pintype "input"))
      (node (ref "IC15") (pin "11") (pinfunction "O_11") (pintype "output"))
    )
    (net (code "140") (name "Net-(IC11A-QA)") (class "Default")
      (node (ref "IC11") (pin "3") (pinfunction "QA_3") (pintype "output"))
      (node (ref "IC14") (pin "11") (pinfunction "A1_11") (pintype "input"))
      (node (ref "IC18") (pin "2") (pinfunction "A1_2") (pintype "input"))
    )
    (net (code "141") (name "Net-(IC11A-QB)") (class "Default")
      (node (ref "IC11") (pin "2") (pinfunction "QB_2") (pintype "output"))
      (node (ref "IC14") (pin "13") (pinfunction "A2_13") (pintype "input"))
      (node (ref "IC18") (pin "4") (pinfunction "A2_4") (pintype "input"))
    )
    (net (code "142") (name "Net-(IC11A-QC)") (class "Default")
      (node (ref "IC11") (pin "6") (pinfunction "QC_6") (pintype "output"))
      (node (ref "IC14") (pin "15") (pinfunction "A3_15") (pintype "input"))
      (node (ref "IC18") (pin "6") (pinfunction "A3_6") (pintype "input"))
    )
    (net (code "143") (name "Net-(IC11A-QD)") (class "Default")
      (node (ref "IC11") (pin "7") (pinfunction "QD_7") (pintype "output"))
      (node (ref "IC14") (pin "17") (pinfunction "A4_17") (pintype "input"))
      (node (ref "IC18") (pin "8") (pinfunction "A4_8") (pintype "input"))
    )
    (net (code "144") (name "Net-(IC12A-QA)") (class "Default")
      (node (ref "IC12") (pin "3") (pinfunction "QA_3") (pintype "output"))
      (node (ref "IC14") (pin "2") (pinfunction "A1_2") (pintype "input"))
      (node (ref "IC18") (pin "11") (pinfunction "A1_11") (pintype "input"))
    )
    (net (code "145") (name "Net-(IC12A-QB)") (class "Default")
      (node (ref "IC12") (pin "2") (pinfunction "QB_2") (pintype "output"))
      (node (ref "IC14") (pin "4") (pinfunction "A2_4") (pintype "input"))
      (node (ref "IC18") (pin "13") (pinfunction "A2_13") (pintype "input"))
    )
    (net (code "146") (name "Net-(IC12A-QC)") (class "Default")
      (node (ref "IC12") (pin "6") (pinfunction "QC_6") (pintype "output"))
      (node (ref "IC14") (pin "6") (pinfunction "A3_6") (pintype "input"))
      (node (ref "IC18") (pin "15") (pinfunction "A3_15") (pintype "input"))
    )
    (net (code "147") (name "Net-(IC12A-QD)") (class "Default")
      (node (ref "IC12") (pin "7") (pinfunction "QD_7") (pintype "output"))
      (node (ref "IC14") (pin "8") (pinfunction "A4_8") (pintype "input"))
      (node (ref "IC18") (pin "17") (pinfunction "A4_17") (pintype "input"))
    )
    (net (code "148") (name "Net-(IC13A-G)") (class "Default")
      (node (ref "IC13") (pin "1") (pinfunction "G_1") (pintype "input"))
      (node (ref "IC13") (pin "19") (pinfunction "G_19") (pintype "input"))
      (node (ref "IC2") (pin "8") (pinfunction "O_8") (pintype "output"))
    )
    (net (code "149") (name "Net-(IC13B-A1)") (class "Default")
      (node (ref "IC13") (pin "11") (pinfunction "A1_11") (pintype "input"))
      (node (ref "IC17") (pin "2") (pinfunction "A1_2") (pintype "input"))
      (node (ref "IC9") (pin "3") (pinfunction "QA_3") (pintype "output"))
    )
    (net (code "150") (name "Net-(IC13B-A2)") (class "Default")
      (node (ref "IC13") (pin "13") (pinfunction "A2_13") (pintype "input"))
      (node (ref "IC17") (pin "4") (pinfunction "A2_4") (pintype "input"))
      (node (ref "IC9") (pin "2") (pinfunction "QB_2") (pintype "output"))
    )
    (net (code "151") (name "Net-(IC13B-A3)") (class "Default")
      (node (ref "IC13") (pin "15") (pinfunction "A3_15") (pintype "input"))
      (node (ref "IC17") (pin "6") (pinfunction "A3_6") (pintype "input"))
      (node (ref "IC9") (pin "6") (pinfunction "QC_6") (pintype "output"))
    )
    (net (code "152") (name "Net-(IC13B-A4)") (class "Default")
      (node (ref "IC13") (pin "17") (pinfunction "A4_17") (pintype "input"))
      (node (ref "IC17") (pin "8") (pinfunction "A4_8") (pintype "input"))
      (node (ref "IC9") (pin "7") (pinfunction "QD_7") (pintype "output"))
    )
    (net (code "153") (name "Net-(IC14A-G)") (class "Default")
      (node (ref "IC14") (pin "1") (pinfunction "G_1") (pintype "input"))
      (node (ref "IC14") (pin "19") (pinfunction "G_19") (pintype "input"))
      (node (ref "IC2") (pin "11") (pinfunction "O_11") (pintype "output"))
    )
    (net (code "154") (name "Net-(IC15A-O)") (class "Default")
      (node (ref "IC15") (pin "3") (pinfunction "O_3") (pintype "output"))
      (node (ref "IC9") (pin "5") (pinfunction "UP_5") (pintype "input"))
    )
    (net (code "155") (name "Net-(IC15B-O)") (class "Default")
      (node (ref "IC15") (pin "6") (pinfunction "O_6") (pintype "output"))
      (node (ref "IC9") (pin "4") (pinfunction "DN_4") (pintype "input"))
    )
    (net (code "156") (name "Net-(IC19A-BO)") (class "Default")
      (node (ref "IC19") (pin "13") (pinfunction "BO_13") (pintype "output"))
      (node (ref "IC20") (pin "4") (pinfunction "DN_4") (pintype "input"))
    )
    (net (code "157") (name "Net-(IC19A-CO)") (class "Default")
      (node (ref "IC19") (pin "12") (pinfunction "CO_12") (pintype "output"))
      (node (ref "IC20") (pin "5") (pinfunction "UP_5") (pintype "input"))
    )
    (net (code "158") (name "Net-(IC19A-DN)") (class "Default")
      (node (ref "IC19") (pin "4") (pinfunction "DN_4") (pintype "input"))
      (node (ref "IC25") (pin "6") (pinfunction "O_6") (pintype "output"))
    )
    (net (code "159") (name "Net-(IC19A-LD)") (class "Default")
      (node (ref "IC19") (pin "11") (pinfunction "LD_11") (pintype "input"))
      (node (ref "IC20") (pin "11") (pinfunction "LD_11") (pintype "input"))
      (node (ref "IC25") (pin "8") (pinfunction "O_8") (pintype "output"))
    )
    (net (code "160") (name "Net-(IC19A-QA)") (class "Default")
      (node (ref "IC19") (pin "3") (pinfunction "QA_3") (pintype "output"))
      (node (ref "IC23") (pin "11") (pinfunction "A1_11") (pintype "input"))
      (node (ref "IC27") (pin "2") (pinfunction "A1_2") (pintype "input"))
    )
    (net (code "161") (name "Net-(IC19A-QB)") (class "Default")
      (node (ref "IC19") (pin "2") (pinfunction "QB_2") (pintype "output"))
      (node (ref "IC23") (pin "13") (pinfunction "A2_13") (pintype "input"))
      (node (ref "IC27") (pin "4") (pinfunction "A2_4") (pintype "input"))
    )
    (net (code "162") (name "Net-(IC19A-QC)") (class "Default")
      (node (ref "IC19") (pin "6") (pinfunction "QC_6") (pintype "output"))
      (node (ref "IC23") (pin "15") (pinfunction "A3_15") (pintype "input"))
      (node (ref "IC27") (pin "6") (pinfunction "A3_6") (pintype "input"))
    )
    (net (code "163") (name "Net-(IC19A-QD)") (class "Default")
      (node (ref "IC19") (pin "7") (pinfunction "QD_7") (pintype "output"))
      (node (ref "IC23") (pin "17") (pinfunction "A4_17") (pintype "input"))
      (node (ref "IC27") (pin "8") (pinfunction "A4_8") (pintype "input"))
    )
    (net (code "164") (name "Net-(IC19A-UP)") (class "Default")
      (node (ref "IC19") (pin "5") (pinfunction "UP_5") (pintype "input"))
      (node (ref "IC25") (pin "3") (pinfunction "O_3") (pintype "output"))
    )
    (net (code "165") (name "Net-(IC20A-BO)") (class "Default")
      (node (ref "IC20") (pin "13") (pinfunction "BO_13") (pintype "output"))
      (node (ref "IC21") (pin "4") (pinfunction "DN_4") (pintype "input"))
    )
    (net (code "166") (name "Net-(IC20A-CO)") (class "Default")
      (node (ref "IC20") (pin "12") (pinfunction "CO_12") (pintype "output"))
      (node (ref "IC21") (pin "5") (pinfunction "UP_5") (pintype "input"))
    )
    (net (code "167") (name "Net-(IC20A-QA)") (class "Default")
      (node (ref "IC20") (pin "3") (pinfunction "QA_3") (pintype "output"))
      (node (ref "IC23") (pin "2") (pinfunction "A1_2") (pintype "input"))
      (node (ref "IC27") (pin "11") (pinfunction "A1_11") (pintype "input"))
    )
    (net (code "168") (name "Net-(IC20A-QB)") (class "Default")
      (node (ref "IC20") (pin "2") (pinfunction "QB_2") (pintype "output"))
      (node (ref "IC23") (pin "4") (pinfunction "A2_4") (pintype "input"))
      (node (ref "IC27") (pin "13") (pinfunction "A2_13") (pintype "input"))
    )
    (net (code "169") (name "Net-(IC20A-QC)") (class "Default")
      (node (ref "IC20") (pin "6") (pinfunction "QC_6") (pintype "output"))
      (node (ref "IC23") (pin "6") (pinfunction "A3_6") (pintype "input"))
      (node (ref "IC27") (pin "15") (pinfunction "A3_15") (pintype "input"))
    )
    (net (code "170") (name "Net-(IC20A-QD)") (class "Default")
      (node (ref "IC20") (pin "7") (pinfunction "QD_7") (pintype "output"))
      (node (ref "IC23") (pin "8") (pinfunction "A4_8") (pintype "input"))
      (node (ref "IC27") (pin "17") (pinfunction "A4_17") (pintype "input"))
    )
    (net (code "171") (name "Net-(IC21A-BO)") (class "Default")
      (node (ref "IC21") (pin "13") (pinfunction "BO_13") (pintype "output"))
      (node (ref "IC22") (pin "4") (pinfunction "DN_4") (pintype "input"))
    )
    (net (code "172") (name "Net-(IC21A-CO)") (class "Default")
      (node (ref "IC21") (pin "12") (pinfunction "CO_12") (pintype "output"))
      (node (ref "IC22") (pin "5") (pinfunction "UP_5") (pintype "input"))
    )
    (net (code "173") (name "Net-(IC21A-LD)") (class "Default")
      (node (ref "IC21") (pin "11") (pinfunction "LD_11") (pintype "input"))
      (node (ref "IC22") (pin "11") (pinfunction "LD_11") (pintype "input"))
      (node (ref "IC25") (pin "11") (pinfunction "O_11") (pintype "output"))
    )
    (net (code "174") (name "Net-(IC21A-QA)") (class "Default")
      (node (ref "IC21") (pin "3") (pinfunction "QA_3") (pintype "output"))
      (node (ref "IC24") (pin "11") (pinfunction "A1_11") (pintype "input"))
      (node (ref "IC28") (pin "2") (pinfunction "A1_2") (pintype "input"))
    )
    (net (code "175") (name "Net-(IC21A-QB)") (class "Default")
      (node (ref "IC21") (pin "2") (pinfunction "QB_2") (pintype "output"))
      (node (ref "IC24") (pin "13") (pinfunction "A2_13") (pintype "input"))
      (node (ref "IC28") (pin "4") (pinfunction "A2_4") (pintype "input"))
    )
    (net (code "176") (name "Net-(IC21A-QC)") (class "Default")
      (node (ref "IC21") (pin "6") (pinfunction "QC_6") (pintype "output"))
      (node (ref "IC24") (pin "15") (pinfunction "A3_15") (pintype "input"))
      (node (ref "IC28") (pin "6") (pinfunction "A3_6") (pintype "input"))
    )
    (net (code "177") (name "Net-(IC21A-QD)") (class "Default")
      (node (ref "IC21") (pin "7") (pinfunction "QD_7") (pintype "output"))
      (node (ref "IC24") (pin "17") (pinfunction "A4_17") (pintype "input"))
      (node (ref "IC28") (pin "8") (pinfunction "A4_8") (pintype "input"))
    )
    (net (code "178") (name "Net-(IC22A-QA)") (class "Default")
      (node (ref "IC22") (pin "3") (pinfunction "QA_3") (pintype "output"))
      (node (ref "IC24") (pin "2") (pinfunction "A1_2") (pintype "input"))
      (node (ref "IC28") (pin "11") (pinfunction "A1_11") (pintype "input"))
    )
    (net (code "179") (name "Net-(IC22A-QB)") (class "Default")
      (node (ref "IC22") (pin "2") (pinfunction "QB_2") (pintype "output"))
      (node (ref "IC24") (pin "4") (pinfunction "A2_4") (pintype "input"))
      (node (ref "IC28") (pin "13") (pinfunction "A2_13") (pintype "input"))
    )
    (net (code "180") (name "Net-(IC22A-QC)") (class "Default")
      (node (ref "IC22") (pin "6") (pinfunction "QC_6") (pintype "output"))
      (node (ref "IC24") (pin "6") (pinfunction "A3_6") (pintype "input"))
      (node (ref "IC28") (pin "15") (pinfunction "A3_15") (pintype "input"))
    )
    (net (code "181") (name "Net-(IC22A-QD)") (class "Default")
      (node (ref "IC22") (pin "7") (pinfunction "QD_7") (pintype "output"))
      (node (ref "IC24") (pin "8") (pinfunction "A4_8") (pintype "input"))
      (node (ref "IC28") (pin "17") (pinfunction "A4_17") (pintype "input"))
    )
    (net (code "182") (name "Net-(IC23A-G)") (class "Default")
      (node (ref "IC23") (pin "1") (pinfunction "G_1") (pintype "input"))
      (node (ref "IC23") (pin "19") (pinfunction "G_19") (pintype "input"))
      (node (ref "IC26") (pin "3") (pinfunction "O_3") (pintype "output"))
    )
    (net (code "183") (name "Net-(IC24A-G)") (class "Default")
      (node (ref "IC24") (pin "1") (pinfunction "G_1") (pintype "input"))
      (node (ref "IC24") (pin "19") (pinfunction "G_19") (pintype "input"))
      (node (ref "IC26") (pin "6") (pinfunction "O_6") (pintype "output"))
    )
    (net (code "184") (name "Net-(IC26C-O)") (class "Default")
      (node (ref "IC26") (pin "8") (pinfunction "O_8") (pintype "output"))
      (node (ref "IC45") (pin "1") (pinfunction "G_1") (pintype "input"))
      (node (ref "IC45") (pin "19") (pinfunction "G_19") (pintype "input"))
    )
    (net (code "185") (name "Net-(IC26D-O)") (class "Default")
      (node (ref "IC26") (pin "11") (pinfunction "O_11") (pintype "output"))
      (node (ref "IC46") (pin "1") (pinfunction "G_1") (pintype "input"))
      (node (ref "IC46") (pin "19") (pinfunction "G_19") (pintype "input"))
    )
    (net (code "186") (name "Net-(IC29A-BO)") (class "Default")
      (node (ref "IC29") (pin "13") (pinfunction "BO_13") (pintype "output"))
      (node (ref "IC30") (pin "4") (pinfunction "DN_4") (pintype "input"))
    )
    (net (code "187") (name "Net-(IC29A-CO)") (class "Default")
      (node (ref "IC29") (pin "12") (pinfunction "CO_12") (pintype "output"))
      (node (ref "IC30") (pin "5") (pinfunction "UP_5") (pintype "input"))
    )
    (net (code "188") (name "Net-(IC29A-DN)") (class "Default")
      (node (ref "IC29") (pin "4") (pinfunction "DN_4") (pintype "input"))
      (node (ref "IC47") (pin "6") (pinfunction "O_6") (pintype "output"))
    )
    (net (code "189") (name "Net-(IC29A-LD)") (class "Default")
      (node (ref "IC29") (pin "11") (pinfunction "LD_11") (pintype "input"))
      (node (ref "IC30") (pin "11") (pinfunction "LD_11") (pintype "input"))
      (node (ref "IC47") (pin "8") (pinfunction "O_8") (pintype "output"))
    )
    (net (code "190") (name "Net-(IC29A-QA)") (class "Default")
      (node (ref "IC29") (pin "3") (pinfunction "QA_3") (pintype "output"))
      (node (ref "IC45") (pin "11") (pinfunction "A1_11") (pintype "input"))
      (node (ref "IC49") (pin "2") (pinfunction "A1_2") (pintype "input"))
    )
    (net (code "191") (name "Net-(IC29A-QB)") (class "Default")
      (node (ref "IC29") (pin "2") (pinfunction "QB_2") (pintype "output"))
      (node (ref "IC45") (pin "13") (pinfunction "A2_13") (pintype "input"))
      (node (ref "IC49") (pin "4") (pinfunction "A2_4") (pintype "input"))
    )
    (net (code "192") (name "Net-(IC29A-QC)") (class "Default")
      (node (ref "IC29") (pin "6") (pinfunction "QC_6") (pintype "output"))
      (node (ref "IC45") (pin "15") (pinfunction "A3_15") (pintype "input"))
      (node (ref "IC49") (pin "6") (pinfunction "A3_6") (pintype "input"))
    )
    (net (code "193") (name "Net-(IC29A-QD)") (class "Default")
      (node (ref "IC29") (pin "7") (pinfunction "QD_7") (pintype "output"))
      (node (ref "IC45") (pin "17") (pinfunction "A4_17") (pintype "input"))
      (node (ref "IC49") (pin "8") (pinfunction "A4_8") (pintype "input"))
    )
    (net (code "194") (name "Net-(IC29A-UP)") (class "Default")
      (node (ref "IC29") (pin "5") (pinfunction "UP_5") (pintype "input"))
      (node (ref "IC47") (pin "3") (pinfunction "O_3") (pintype "output"))
    )
    (net (code "195") (name "Net-(IC30A-BO)") (class "Default")
      (node (ref "IC30") (pin "13") (pinfunction "BO_13") (pintype "output"))
      (node (ref "IC43") (pin "4") (pinfunction "DN_4") (pintype "input"))
    )
    (net (code "196") (name "Net-(IC30A-CO)") (class "Default")
      (node (ref "IC30") (pin "12") (pinfunction "CO_12") (pintype "output"))
      (node (ref "IC43") (pin "5") (pinfunction "UP_5") (pintype "input"))
    )
    (net (code "197") (name "Net-(IC30A-QA)") (class "Default")
      (node (ref "IC30") (pin "3") (pinfunction "QA_3") (pintype "output"))
      (node (ref "IC45") (pin "2") (pinfunction "A1_2") (pintype "input"))
      (node (ref "IC49") (pin "11") (pinfunction "A1_11") (pintype "input"))
    )
    (net (code "198") (name "Net-(IC30A-QB)") (class "Default")
      (node (ref "IC30") (pin "2") (pinfunction "QB_2") (pintype "output"))
      (node (ref "IC45") (pin "4") (pinfunction "A2_4") (pintype "input"))
      (node (ref "IC49") (pin "13") (pinfunction "A2_13") (pintype "input"))
    )
    (net (code "199") (name "Net-(IC30A-QC)") (class "Default")
      (node (ref "IC30") (pin "6") (pinfunction "QC_6") (pintype "output"))
      (node (ref "IC45") (pin "6") (pinfunction "A3_6") (pintype "input"))
      (node (ref "IC49") (pin "15") (pinfunction "A3_15") (pintype "input"))
    )
    (net (code "200") (name "Net-(IC30A-QD)") (class "Default")
      (node (ref "IC30") (pin "7") (pinfunction "QD_7") (pintype "output"))
      (node (ref "IC45") (pin "8") (pinfunction "A4_8") (pintype "input"))
      (node (ref "IC49") (pin "17") (pinfunction "A4_17") (pintype "input"))
    )
    (net (code "201") (name "Net-(IC31A-O)") (class "Default")
      (node (ref "IC31") (pin "3") (pinfunction "O_3") (pintype "output"))
      (node (ref "IC32") (pin "1") (pinfunction "G_1") (pintype "input"))
    )
    (net (code "202") (name "Net-(IC31B-O)") (class "Default")
      (node (ref "IC31") (pin "6") (pinfunction "O_6") (pintype "output"))
      (node (ref "IC32") (pin "15") (pinfunction "G_15") (pintype "input"))
    )
    (net (code "203") (name "Net-(IC31C-I0)") (class "Default")
      (node (ref "IC31") (pin "9") (pinfunction "I0_9") (pintype "input"))
      (node (ref "IC34") (pin "10") (pinfunction "O_10") (pintype "output"))
    )
    (net (code "204") (name "Net-(IC31C-I1)") (class "Default")
      (node (ref "IC31") (pin "10") (pinfunction "I1_10") (pintype "input"))
      (node (ref "IC31") (pin "12") (pinfunction "I0_12") (pintype "input"))
      (node (ref "IC34") (pin "11") (pinfunction "O_11") (pintype "output"))
    )
    (net (code "205") (name "Net-(IC31C-O)") (class "Default")
      (node (ref "IC31") (pin "8") (pinfunction "O_8") (pintype "output"))
      (node (ref "IC35") (pin "19") (pinfunction "G_19") (pintype "input"))
      (node (ref "IC36") (pin "19") (pinfunction "G_19") (pintype "input"))
    )
    (net (code "206") (name "Net-(IC31D-O)") (class "Default")
      (node (ref "IC31") (pin "11") (pinfunction "O_11") (pintype "output"))
      (node (ref "IC37") (pin "19") (pinfunction "G_19") (pintype "input"))
    )
    (net (code "207") (name "Net-(IC32A-Y1)") (class "Default")
      (node (ref "IC32") (pin "5") (pinfunction "Y1_5") (pintype "output"))
      (node (ref "J1") (pin "3") (pinfunction "3_3") (pintype "passive"))
    )
    (net (code "208") (name "Net-(IC32A-Y2)") (class "Default")
      (node (ref "IC32") (pin "6") (pinfunction "Y2_6") (pintype "output"))
      (node (ref "J1") (pin "5") (pinfunction "5_5") (pintype "passive"))
    )
    (net (code "209") (name "Net-(IC32A-Y3)") (class "Default")
      (node (ref "IC32") (pin "7") (pinfunction "Y3_7") (pintype "output"))
      (node (ref "J1") (pin "7") (pinfunction "7_7") (pintype "passive"))
    )
    (net (code "210") (name "Net-(IC32B-Y1)") (class "Default")
      (node (ref "IC32") (pin "11") (pinfunction "Y1_11") (pintype "output"))
      (node (ref "J2") (pin "3") (pinfunction "3_3") (pintype "passive"))
    )
    (net (code "211") (name "Net-(IC32B-Y2)") (class "Default")
      (node (ref "IC32") (pin "10") (pinfunction "Y2_10") (pintype "output"))
      (node (ref "J2") (pin "5") (pinfunction "5_5") (pintype "passive"))
    )
    (net (code "212") (name "Net-(IC32B-Y3)") (class "Default")
      (node (ref "IC32") (pin "9") (pinfunction "Y3_9") (pintype "output"))
      (node (ref "J2") (pin "7") (pinfunction "7_7") (pintype "passive"))
    )
    (net (code "213") (name "Net-(IC38B-G)") (class "Default")
      (node (ref "IC38") (pin "15") (pinfunction "G_15") (pintype "input"))
      (node (ref "IC40") (pin "3") (pinfunction "O_3") (pintype "output"))
    )
    (net (code "214") (name "Net-(IC38B-Y1)") (class "Default")
      (node (ref "IC38") (pin "11") (pinfunction "Y1_11") (pintype "output"))
      (node (ref "J3") (pin "3") (pinfunction "3_3") (pintype "passive"))
    )
    (net (code "215") (name "Net-(IC38B-Y2)") (class "Default")
      (node (ref "IC38") (pin "10") (pinfunction "Y2_10") (pintype "output"))
      (node (ref "J3") (pin "5") (pinfunction "5_5") (pintype "passive"))
    )
    (net (code "216") (name "Net-(IC38B-Y3)") (class "Default")
      (node (ref "IC38") (pin "9") (pinfunction "Y3_9") (pintype "output"))
      (node (ref "J3") (pin "7") (pinfunction "7_7") (pintype "passive"))
    )
    (net (code "217") (name "Net-(IC41B-A1)") (class "Default")
      (node (ref "IC4") (pin "3") (pinfunction "QA_3") (pintype "output"))
      (node (ref "IC41") (pin "11") (pinfunction "A1_11") (pintype "input"))
      (node (ref "IC7") (pin "2") (pinfunction "A1_2") (pintype "input"))
    )
    (net (code "218") (name "Net-(IC41B-A2)") (class "Default")
      (node (ref "IC4") (pin "2") (pinfunction "QB_2") (pintype "output"))
      (node (ref "IC41") (pin "13") (pinfunction "A2_13") (pintype "input"))
      (node (ref "IC7") (pin "4") (pinfunction "A2_4") (pintype "input"))
    )
    (net (code "219") (name "Net-(IC41B-A3)") (class "Default")
      (node (ref "IC4") (pin "6") (pinfunction "QC_6") (pintype "output"))
      (node (ref "IC41") (pin "15") (pinfunction "A3_15") (pintype "input"))
      (node (ref "IC7") (pin "6") (pinfunction "A3_6") (pintype "input"))
    )
    (net (code "220") (name "Net-(IC41B-A4)") (class "Default")
      (node (ref "IC4") (pin "7") (pinfunction "QD_7") (pintype "output"))
      (node (ref "IC41") (pin "17") (pinfunction "A4_17") (pintype "input"))
      (node (ref "IC7") (pin "8") (pinfunction "A4_8") (pintype "input"))
    )
    (net (code "221") (name "Net-(IC42A-A1)") (class "Default")
      (node (ref "IC42") (pin "2") (pinfunction "A1_2") (pintype "input"))
      (node (ref "IC5") (pin "3") (pinfunction "QA_3") (pintype "output"))
      (node (ref "IC8") (pin "11") (pinfunction "A1_11") (pintype "input"))
    )
    (net (code "222") (name "Net-(IC42A-A2)") (class "Default")
      (node (ref "IC42") (pin "4") (pinfunction "A2_4") (pintype "input"))
      (node (ref "IC5") (pin "2") (pinfunction "QB_2") (pintype "output"))
      (node (ref "IC8") (pin "13") (pinfunction "A2_13") (pintype "input"))
    )
    (net (code "223") (name "Net-(IC42A-A3)") (class "Default")
      (node (ref "IC42") (pin "6") (pinfunction "A3_6") (pintype "input"))
      (node (ref "IC5") (pin "6") (pinfunction "QC_6") (pintype "output"))
      (node (ref "IC8") (pin "15") (pinfunction "A3_15") (pintype "input"))
    )
    (net (code "224") (name "Net-(IC42A-A4)") (class "Default")
      (node (ref "IC42") (pin "8") (pinfunction "A4_8") (pintype "input"))
      (node (ref "IC5") (pin "7") (pinfunction "QD_7") (pintype "output"))
      (node (ref "IC8") (pin "17") (pinfunction "A4_17") (pintype "input"))
    )
    (net (code "225") (name "Net-(IC42B-A1)") (class "Default")
      (node (ref "IC42") (pin "11") (pinfunction "A1_11") (pintype "input"))
      (node (ref "IC6") (pin "3") (pinfunction "QA_3") (pintype "output"))
      (node (ref "IC8") (pin "2") (pinfunction "A1_2") (pintype "input"))
    )
    (net (code "226") (name "Net-(IC42B-A2)") (class "Default")
      (node (ref "IC42") (pin "13") (pinfunction "A2_13") (pintype "input"))
      (node (ref "IC6") (pin "2") (pinfunction "QB_2") (pintype "output"))
      (node (ref "IC8") (pin "4") (pinfunction "A2_4") (pintype "input"))
    )
    (net (code "227") (name "Net-(IC42B-A3)") (class "Default")
      (node (ref "IC42") (pin "15") (pinfunction "A3_15") (pintype "input"))
      (node (ref "IC6") (pin "6") (pinfunction "QC_6") (pintype "output"))
      (node (ref "IC8") (pin "6") (pinfunction "A3_6") (pintype "input"))
    )
    (net (code "228") (name "Net-(IC42B-A4)") (class "Default")
      (node (ref "IC42") (pin "17") (pinfunction "A4_17") (pintype "input"))
      (node (ref "IC6") (pin "7") (pinfunction "QD_7") (pintype "output"))
      (node (ref "IC8") (pin "8") (pinfunction "A4_8") (pintype "input"))
    )
    (net (code "229") (name "Net-(IC43A-BO)") (class "Default")
      (node (ref "IC43") (pin "13") (pinfunction "BO_13") (pintype "output"))
      (node (ref "IC44") (pin "4") (pinfunction "DN_4") (pintype "input"))
    )
    (net (code "230") (name "Net-(IC43A-CO)") (class "Default")
      (node (ref "IC43") (pin "12") (pinfunction "CO_12") (pintype "output"))
      (node (ref "IC44") (pin "5") (pinfunction "UP_5") (pintype "input"))
    )
    (net (code "231") (name "Net-(IC43A-LD)") (class "Default")
      (node (ref "IC43") (pin "11") (pinfunction "LD_11") (pintype "input"))
      (node (ref "IC44") (pin "11") (pinfunction "LD_11") (pintype "input"))
      (node (ref "IC47") (pin "11") (pinfunction "O_11") (pintype "output"))
    )
    (net (code "232") (name "Net-(IC43A-QA)") (class "Default")
      (node (ref "IC43") (pin "3") (pinfunction "QA_3") (pintype "output"))
      (node (ref "IC46") (pin "11") (pinfunction "A1_11") (pintype "input"))
      (node (ref "IC50") (pin "2") (pinfunction "A1_2") (pintype "input"))
    )
    (net (code "233") (name "Net-(IC43A-QB)") (class "Default")
      (node (ref "IC43") (pin "2") (pinfunction "QB_2") (pintype "output"))
      (node (ref "IC46") (pin "13") (pinfunction "A2_13") (pintype "input"))
      (node (ref "IC50") (pin "4") (pinfunction "A2_4") (pintype "input"))
    )
    (net (code "234") (name "Net-(IC43A-QC)") (class "Default")
      (node (ref "IC43") (pin "6") (pinfunction "QC_6") (pintype "output"))
      (node (ref "IC46") (pin "15") (pinfunction "A3_15") (pintype "input"))
      (node (ref "IC50") (pin "6") (pinfunction "A3_6") (pintype "input"))
    )
    (net (code "235") (name "Net-(IC43A-QD)") (class "Default")
      (node (ref "IC43") (pin "7") (pinfunction "QD_7") (pintype "output"))
      (node (ref "IC46") (pin "17") (pinfunction "A4_17") (pintype "input"))
      (node (ref "IC50") (pin "8") (pinfunction "A4_8") (pintype "input"))
    )
    (net (code "236") (name "Net-(IC44A-QA)") (class "Default")
      (node (ref "IC44") (pin "3") (pinfunction "QA_3") (pintype "output"))
      (node (ref "IC46") (pin "2") (pinfunction "A1_2") (pintype "input"))
      (node (ref "IC50") (pin "11") (pinfunction "A1_11") (pintype "input"))
    )
    (net (code "237") (name "Net-(IC44A-QB)") (class "Default")
      (node (ref "IC44") (pin "2") (pinfunction "QB_2") (pintype "output"))
      (node (ref "IC46") (pin "4") (pinfunction "A2_4") (pintype "input"))
      (node (ref "IC50") (pin "13") (pinfunction "A2_13") (pintype "input"))
    )
    (net (code "238") (name "Net-(IC44A-QC)") (class "Default")
      (node (ref "IC44") (pin "6") (pinfunction "QC_6") (pintype "output"))
      (node (ref "IC46") (pin "6") (pinfunction "A3_6") (pintype "input"))
      (node (ref "IC50") (pin "15") (pinfunction "A3_15") (pintype "input"))
    )
    (net (code "239") (name "Net-(IC44A-QD)") (class "Default")
      (node (ref "IC44") (pin "7") (pinfunction "QD_7") (pintype "output"))
      (node (ref "IC46") (pin "8") (pinfunction "A4_8") (pintype "input"))
      (node (ref "IC50") (pin "17") (pinfunction "A4_17") (pintype "input"))
    )
    (net (code "240") (name "Net-(PWR-PadA)") (class "Default")
      (node (ref "PWR") (pin "A") (pinfunction "A_A") (pintype "passive"))
      (node (ref "R1") (pin "1") (pinfunction "1_1") (pintype "passive"))
    )
    (net (code "241") (name "OUT") (class "Default")
      (node (ref "X1") (pin "C27") (pinfunction "B_C27") (pintype "passive"))
    )
    (net (code "242") (name "REG-LD-ID0") (class "Default")
      (node (ref "IC33") (pin "14") (pinfunction "A_14") (pintype "input"))
      (node (ref "X1") (pin "B13") (pinfunction "B_B13") (pintype "passive"))
    )
    (net (code "243") (name "REG-LD-ID1") (class "Default")
      (node (ref "IC33") (pin "13") (pinfunction "B_13") (pintype "input"))
      (node (ref "X1") (pin "B14") (pinfunction "B_B14") (pintype "passive"))
    )
    (net (code "244") (name "REG-LD-ID2") (class "Default")
      (node (ref "IC32") (pin "14") (pinfunction "A_14") (pintype "input"))
      (node (ref "X1") (pin "B15") (pinfunction "B_B15") (pintype "passive"))
    )
    (net (code "245") (name "REG-LD-ID3") (class "Default")
      (node (ref "IC32") (pin "13") (pinfunction "B_13") (pintype "input"))
      (node (ref "X1") (pin "B16") (pinfunction "B_B16") (pintype "passive"))
    )
    (net (code "246") (name "REG-RD-ID0") (class "Default")
      (node (ref "IC33") (pin "2") (pinfunction "A_2") (pintype "input"))
      (node (ref "X1") (pin "B9") (pinfunction "B_B9") (pintype "passive"))
    )
    (net (code "247") (name "REG-RD-ID1") (class "Default")
      (node (ref "IC33") (pin "3") (pinfunction "B_3") (pintype "input"))
      (node (ref "X1") (pin "B10") (pinfunction "B_B10") (pintype "passive"))
    )
    (net (code "248") (name "REG-RD-ID2") (class "Default")
      (node (ref "IC32") (pin "2") (pinfunction "A_2") (pintype "input"))
      (node (ref "X1") (pin "B11") (pinfunction "B_B11") (pintype "passive"))
    )
    (net (code "249") (name "REG-RD-ID3") (class "Default")
      (node (ref "IC32") (pin "3") (pinfunction "B_3") (pintype "input"))
      (node (ref "X1") (pin "B12") (pinfunction "B_B12") (pintype "passive"))
    )
    (net (code "250") (name "RESET") (class "Default")
      (node (ref "IC10") (pin "14") (pinfunction "CLR_14") (pintype "input"))
      (node (ref "IC11") (pin "14") (pinfunction "CLR_14") (pintype "input"))
      (node (ref "IC12") (pin "14") (pinfunction "CLR_14") (pintype "input"))
      (node (ref "IC19") (pin "14") (pinfunction "CLR_14") (pintype "input"))
      (node (ref "IC20") (pin "14") (pinfunction "CLR_14") (pintype "input"))
      (node (ref "IC21") (pin "14") (pinfunction "CLR_14") (pintype "input"))
      (node (ref "IC22") (pin "14") (pinfunction "CLR_14") (pintype "input"))
      (node (ref "IC29") (pin "14") (pinfunction "CLR_14") (pintype "input"))
      (node (ref "IC3") (pin "14") (pinfunction "CLR_14") (pintype "input"))
      (node (ref "IC30") (pin "14") (pinfunction "CLR_14") (pintype "input"))
      (node (ref "IC34") (pin "3") (pinfunction "O_3") (pintype "output"))
      (node (ref "IC4") (pin "14") (pinfunction "CLR_14") (pintype "input"))
      (node (ref "IC43") (pin "14") (pinfunction "CLR_14") (pintype "input"))
      (node (ref "IC44") (pin "14") (pinfunction "CLR_14") (pintype "input"))
      (node (ref "IC5") (pin "14") (pinfunction "CLR_14") (pintype "input"))
      (node (ref "IC6") (pin "14") (pinfunction "CLR_14") (pintype "input"))
      (node (ref "IC9") (pin "14") (pinfunction "CLR_14") (pintype "input"))
    )
    (net (code "251") (name "VCC") (class "Default")
      (node (ref "C1") (pin "1") (pinfunction "1_1") (pintype "passive"))
      (node (ref "C10") (pin "1") (pinfunction "1_1") (pintype "passive"))
      (node (ref "C11") (pin "1") (pinfunction "1_1") (pintype "passive"))
      (node (ref "C12") (pin "1") (pinfunction "1_1") (pintype "passive"))
      (node (ref "C13") (pin "1") (pinfunction "1_1") (pintype "passive"))
      (node (ref "C14") (pin "1") (pinfunction "1_1") (pintype "passive"))
      (node (ref "C15") (pin "1") (pinfunction "1_1") (pintype "passive"))
      (node (ref "C16") (pin "1") (pinfunction "1_1") (pintype "passive"))
      (node (ref "C17") (pin "1") (pinfunction "1_1") (pintype "passive"))
      (node (ref "C18") (pin "1") (pinfunction "1_1") (pintype "passive"))
      (node (ref "C19") (pin "1") (pinfunction "1_1") (pintype "passive"))
      (node (ref "C2") (pin "1") (pinfunction "1_1") (pintype "passive"))
      (node (ref "C20") (pin "1") (pinfunction "1_1") (pintype "passive"))
      (node (ref "C21") (pin "1") (pinfunction "1_1") (pintype "passive"))
      (node (ref "C22") (pin "1") (pinfunction "1_1") (pintype "passive"))
      (node (ref "C23") (pin "1") (pinfunction "1_1") (pintype "passive"))
      (node (ref "C24") (pin "1") (pinfunction "1_1") (pintype "passive"))
      (node (ref "C25") (pin "1") (pinfunction "1_1") (pintype "passive"))
      (node (ref "C26") (pin "1") (pinfunction "1_1") (pintype "passive"))
      (node (ref "C27") (pin "1") (pinfunction "1_1") (pintype "passive"))
      (node (ref "C28") (pin "1") (pinfunction "1_1") (pintype "passive"))
      (node (ref "C29") (pin "1") (pinfunction "1_1") (pintype "passive"))
      (node (ref "C3") (pin "1") (pinfunction "1_1") (pintype "passive"))
      (node (ref "C30") (pin "1") (pinfunction "1_1") (pintype "passive"))
      (node (ref "C31") (pin "1") (pinfunction "1_1") (pintype "passive"))
      (node (ref "C32") (pin "1") (pinfunction "1_1") (pintype "passive"))
      (node (ref "C33") (pin "1") (pinfunction "1_1") (pintype "passive"))
      (node (ref "C34") (pin "1") (pinfunction "1_1") (pintype "passive"))
      (node (ref "C35") (pin "1") (pinfunction "1_1") (pintype "passive"))
      (node (ref "C36") (pin "1") (pinfunction "1_1") (pintype "passive"))
      (node (ref "C37") (pin "1") (pinfunction "1_1") (pintype "passive"))
      (node (ref "C38") (pin "1") (pinfunction "1_1") (pintype "passive"))
      (node (ref "C39") (pin "1") (pinfunction "1_1") (pintype "passive"))
      (node (ref "C4") (pin "1") (pinfunction "1_1") (pintype "passive"))
      (node (ref "C40") (pin "1") (pinfunction "1_1") (pintype "passive"))
      (node (ref "C41") (pin "1") (pinfunction "1_1") (pintype "passive"))
      (node (ref "C42") (pin "1") (pinfunction "1_1") (pintype "passive"))
      (node (ref "C43") (pin "1") (pinfunction "1_1") (pintype "passive"))
      (node (ref "C44") (pin "1") (pinfunction "1_1") (pintype "passive"))
      (node (ref "C45") (pin "1") (pinfunction "1_1") (pintype "passive"))
      (node (ref "C46") (pin "1") (pinfunction "1_1") (pintype "passive"))
      (node (ref "C47") (pin "1") (pinfunction "1_1") (pintype "passive"))
      (node (ref "C5") (pin "1") (pinfunction "1_1") (pintype "passive"))
      (node (ref "C6") (pin "1") (pinfunction "1_1") (pintype "passive"))
      (node (ref "C7") (pin "1") (pinfunction "1_1") (pintype "passive"))
      (node (ref "C8") (pin "1") (pinfunction "1_1") (pintype "passive"))
      (node (ref "C9") (pin "1") (pinfunction "1_1") (pintype "passive"))
      (node (ref "IC34") (pin "14") (pinfunction "VDD_14") (pintype "power_in"))
      (node (ref "R1") (pin "2") (pinfunction "2_2") (pintype "passive"))
      (node (ref "RN1") (pin "1") (pinfunction "1_1") (pintype "passive"))
      (node (ref "RN2") (pin "1") (pinfunction "1_1") (pintype "passive"))
      (node (ref "X1") (pin "A2") (pinfunction "B_A2") (pintype "passive"))
      (node (ref "X1") (pin "A31") (pinfunction "B_A31") (pintype "passive"))
      (node (ref "X1") (pin "B2") (pinfunction "B_B2") (pintype "passive"))
      (node (ref "X1") (pin "B31") (pinfunction "B_B31") (pintype "passive"))
      (node (ref "X1") (pin "C2") (pinfunction "B_C2") (pintype "passive"))
      (node (ref "X1") (pin "C31") (pinfunction "B_C31") (pintype "passive"))
    )
    (net (code "252") (name "unconnected-(IC6A-BO-Pad13)") (class "Default")
      (node (ref "IC6") (pin "13") (pinfunction "BO_13") (pintype "output"))
    )
    (net (code "253") (name "unconnected-(IC6A-CO-Pad12)") (class "Default")
      (node (ref "IC6") (pin "12") (pinfunction "CO_12") (pintype "output"))
    )
    (net (code "254") (name "unconnected-(IC12A-BO-Pad13)") (class "Default")
      (node (ref "IC12") (pin "13") (pinfunction "BO_13") (pintype "output"))
    )
    (net (code "255") (name "unconnected-(IC12A-CO-Pad12)") (class "Default")
      (node (ref "IC12") (pin "12") (pinfunction "CO_12") (pintype "output"))
    )
    (net (code "256") (name "unconnected-(IC22A-BO-Pad13)") (class "Default")
      (node (ref "IC22") (pin "13") (pinfunction "BO_13") (pintype "output"))
    )
    (net (code "257") (name "unconnected-(IC22A-CO-Pad12)") (class "Default")
      (node (ref "IC22") (pin "12") (pinfunction "CO_12") (pintype "output"))
    )
    (net (code "258") (name "unconnected-(IC40B-O-Pad6)") (class "Default")
      (node (ref "IC40") (pin "6") (pinfunction "O_6") (pintype "output"))
    )
    (net (code "259") (name "unconnected-(IC40C-O-Pad8)") (class "Default")
      (node (ref "IC40") (pin "8") (pinfunction "O_8") (pintype "output"))
    )
    (net (code "260") (name "unconnected-(IC40D-O-Pad11)") (class "Default")
      (node (ref "IC40") (pin "11") (pinfunction "O_11") (pintype "output"))
    )
    (net (code "261") (name "unconnected-(IC44A-BO-Pad13)") (class "Default")
      (node (ref "IC44") (pin "13") (pinfunction "BO_13") (pintype "output"))
    )
    (net (code "262") (name "unconnected-(IC44A-CO-Pad12)") (class "Default")
      (node (ref "IC44") (pin "12") (pinfunction "CO_12") (pintype "output"))
    )
  )
)
